# StepperBoard.net
KiCad netlist of a schematic drawn in EAGLE
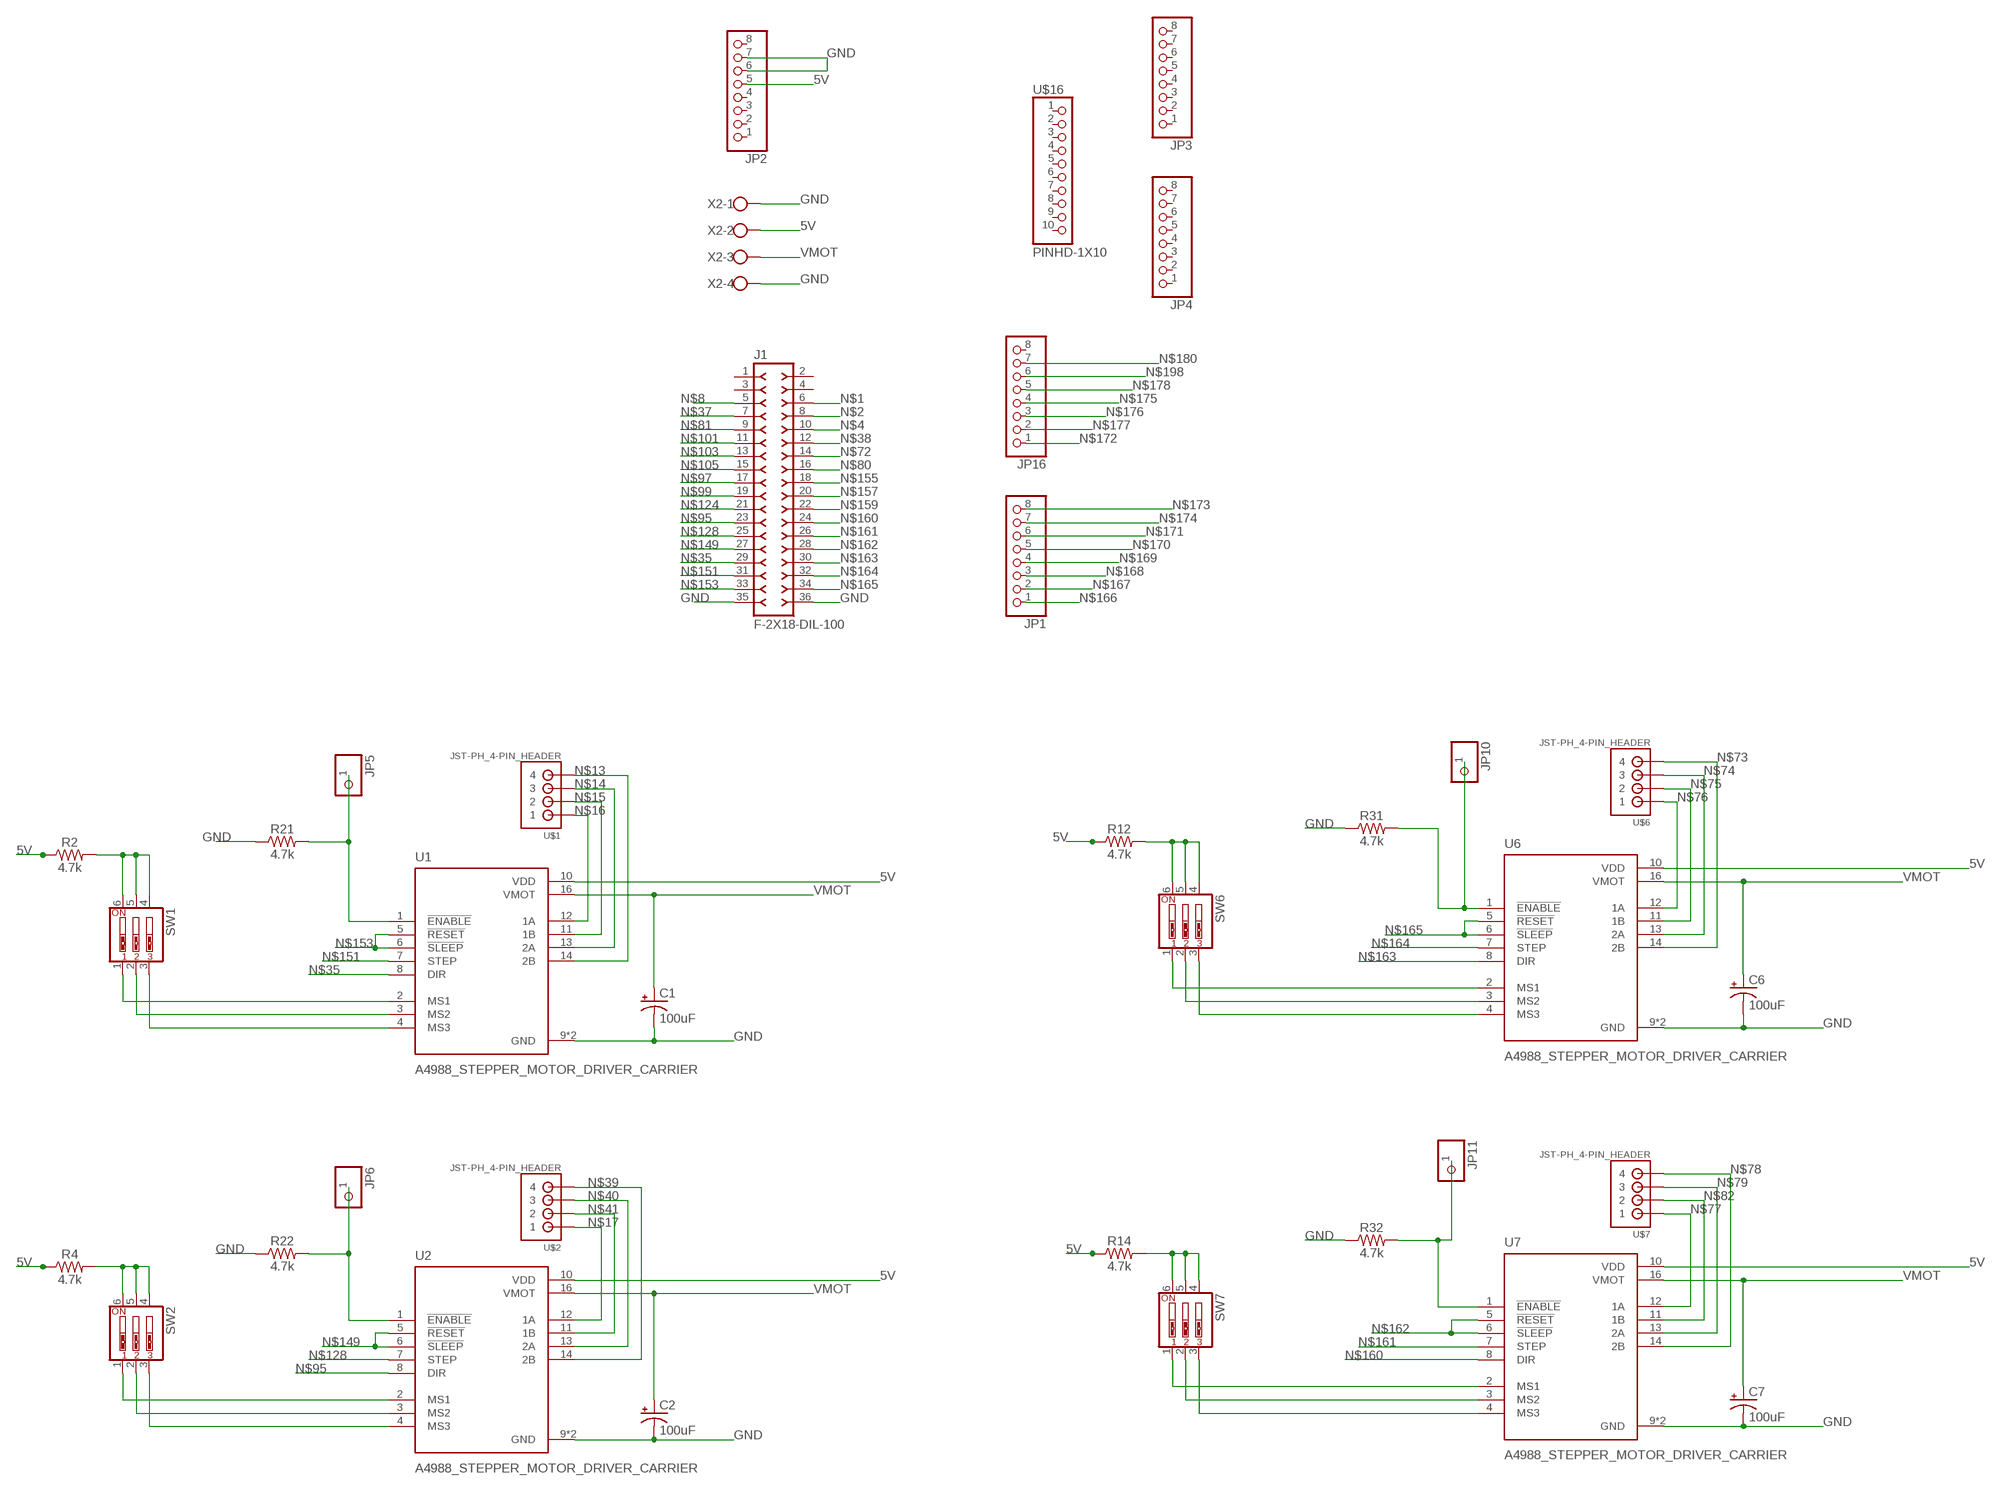
[diagram p0: schematic, sheet 1, part 1 of 3]
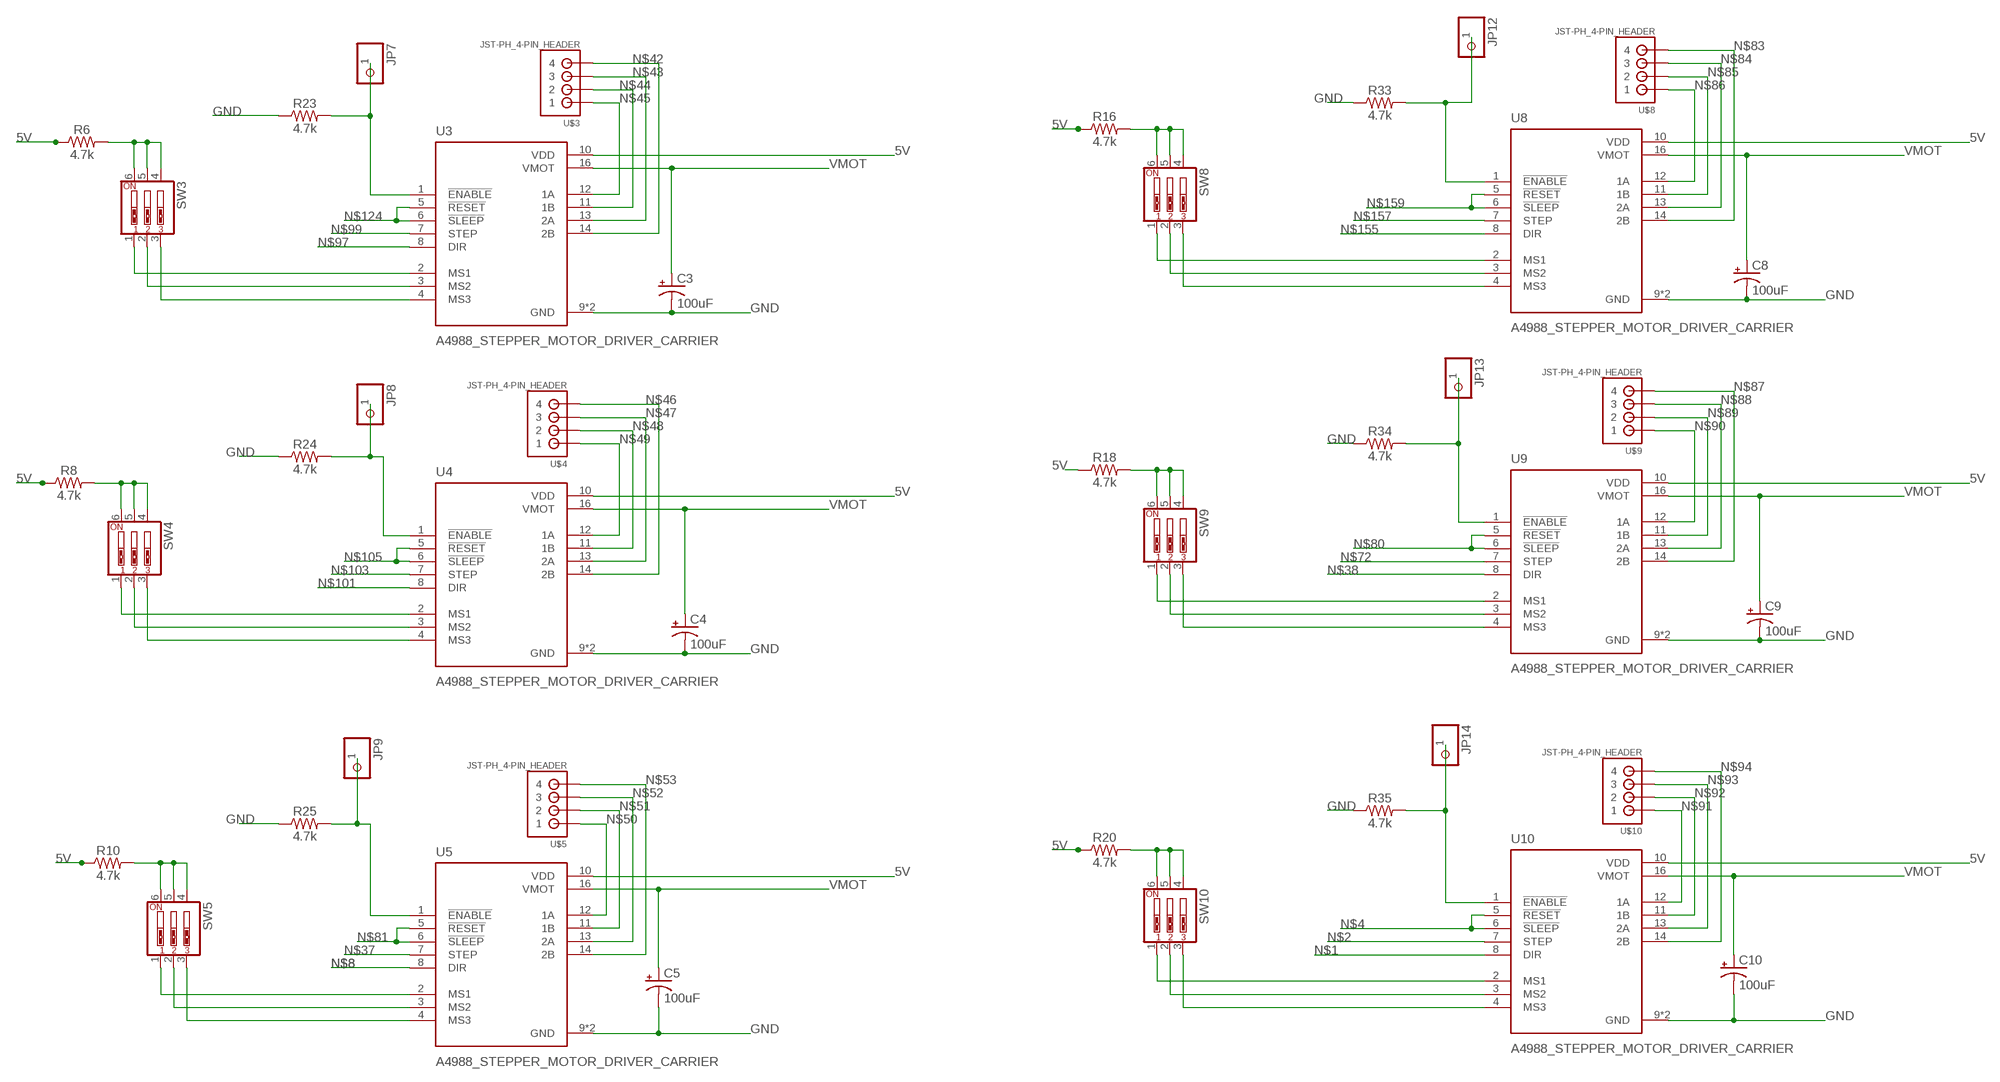
[diagram p1: schematic, sheet 1, part 2 of 3]
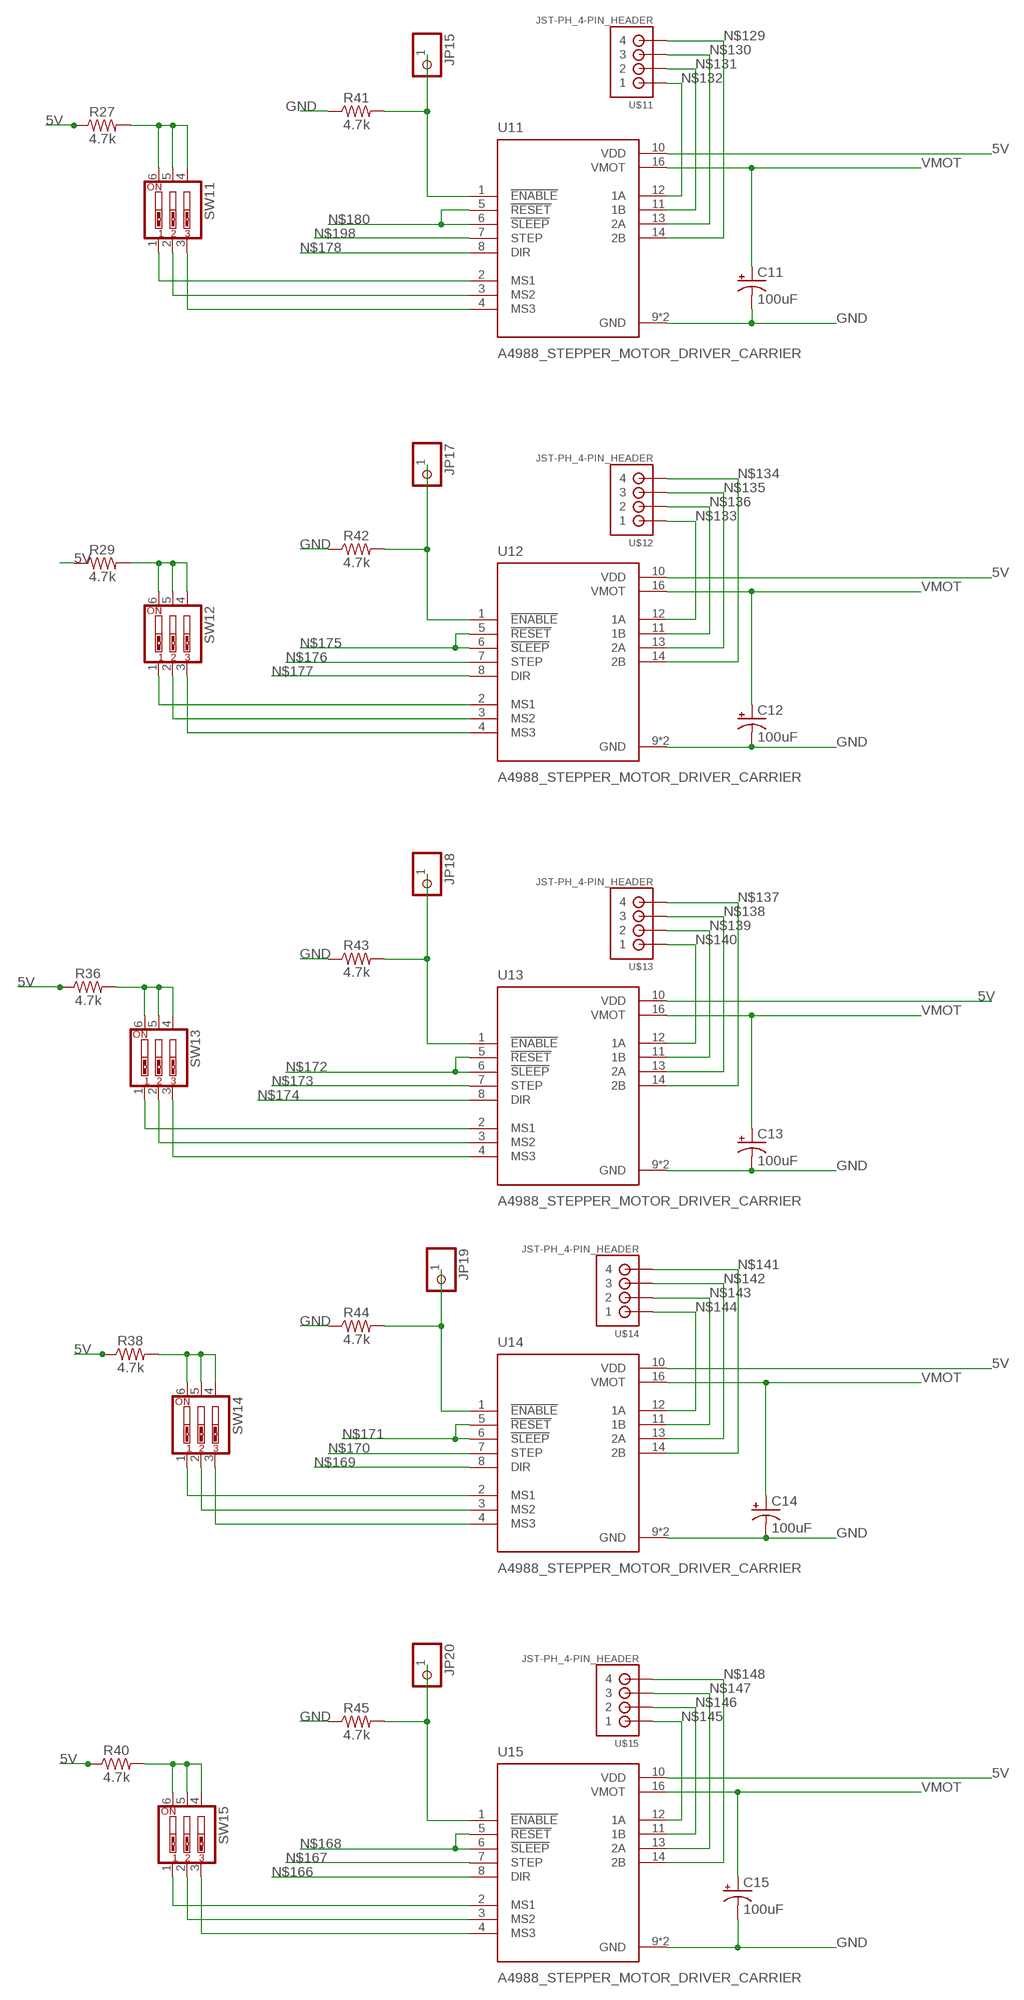
[diagram p2: schematic, sheet 1, part 3 of 3]

(export (version "E")
  (design (tool "Eeschema 10.0.6"))
  (components
    (comp (ref "C1")
      (value "100uF")
      (footprint "eagle-import:CPOL-RADIAL-2.5MM-6.5MM")
      (libsource (lib "eagle-import") (part "100UF-POLAR-RADIAL-2.5MM-25V-20%"))
    )
    (comp (ref "C2")
      (value "100uF")
      (footprint "eagle-import:CPOL-RADIAL-2.5MM-6.5MM")
      (libsource (lib "eagle-import") (part "100UF-POLAR-RADIAL-2.5MM-25V-20%"))
    )
    (comp (ref "C3")
      (value "100uF")
      (footprint "eagle-import:CPOL-RADIAL-2.5MM-6.5MM")
      (libsource (lib "eagle-import") (part "100UF-POLAR-RADIAL-2.5MM-25V-20%"))
    )
    (comp (ref "C4")
      (value "100uF")
      (footprint "eagle-import:CPOL-RADIAL-2.5MM-6.5MM")
      (libsource (lib "eagle-import") (part "100UF-POLAR-RADIAL-2.5MM-25V-20%"))
    )
    (comp (ref "C5")
      (value "100uF")
      (footprint "eagle-import:CPOL-RADIAL-2.5MM-6.5MM")
      (libsource (lib "eagle-import") (part "100UF-POLAR-RADIAL-2.5MM-25V-20%"))
    )
    (comp (ref "C6")
      (value "100uF")
      (footprint "eagle-import:CPOL-RADIAL-2.5MM-6.5MM")
      (libsource (lib "eagle-import") (part "100UF-POLAR-RADIAL-2.5MM-25V-20%"))
    )
    (comp (ref "C7")
      (value "100uF")
      (footprint "eagle-import:CPOL-RADIAL-2.5MM-6.5MM")
      (libsource (lib "eagle-import") (part "100UF-POLAR-RADIAL-2.5MM-25V-20%"))
    )
    (comp (ref "C8")
      (value "100uF")
      (footprint "eagle-import:CPOL-RADIAL-2.5MM-6.5MM")
      (libsource (lib "eagle-import") (part "100UF-POLAR-RADIAL-2.5MM-25V-20%"))
    )
    (comp (ref "C9")
      (value "100uF")
      (footprint "eagle-import:CPOL-RADIAL-2.5MM-6.5MM")
      (libsource (lib "eagle-import") (part "100UF-POLAR-RADIAL-2.5MM-25V-20%"))
    )
    (comp (ref "C10")
      (value "100uF")
      (footprint "eagle-import:CPOL-RADIAL-2.5MM-6.5MM")
      (libsource (lib "eagle-import") (part "100UF-POLAR-RADIAL-2.5MM-25V-20%"))
    )
    (comp (ref "C11")
      (value "100uF")
      (footprint "eagle-import:CPOL-RADIAL-2.5MM-6.5MM")
      (libsource (lib "eagle-import") (part "100UF-POLAR-RADIAL-2.5MM-25V-20%"))
    )
    (comp (ref "C12")
      (value "100uF")
      (footprint "eagle-import:CPOL-RADIAL-2.5MM-6.5MM")
      (libsource (lib "eagle-import") (part "100UF-POLAR-RADIAL-2.5MM-25V-20%"))
    )
    (comp (ref "C13")
      (value "100uF")
      (footprint "eagle-import:CPOL-RADIAL-2.5MM-6.5MM")
      (libsource (lib "eagle-import") (part "100UF-POLAR-RADIAL-2.5MM-25V-20%"))
    )
    (comp (ref "C14")
      (value "100uF")
      (footprint "eagle-import:CPOL-RADIAL-2.5MM-6.5MM")
      (libsource (lib "eagle-import") (part "100UF-POLAR-RADIAL-2.5MM-25V-20%"))
    )
    (comp (ref "C15")
      (value "100uF")
      (footprint "eagle-import:CPOL-RADIAL-2.5MM-6.5MM")
      (libsource (lib "eagle-import") (part "100UF-POLAR-RADIAL-2.5MM-25V-20%"))
    )
    (comp (ref "J1")
      (value "F-2X18-DIL-100")
      (footprint "eagle-import:DIL-100-2X18")
      (libsource (lib "eagle-import") (part "F-2X18-DIL-100"))
    )
    (comp (ref "JP1")
      (value "PINHD-1X8")
      (footprint "eagle-import:1X08")
      (libsource (lib "eagle-import") (part "PINHD-1X8"))
    )
    (comp (ref "JP2")
      (value "PINHD-1X8")
      (footprint "eagle-import:1X08")
      (libsource (lib "eagle-import") (part "PINHD-1X8"))
    )
    (comp (ref "JP3")
      (value "PINHD-1X8")
      (footprint "eagle-import:1X08")
      (libsource (lib "eagle-import") (part "PINHD-1X8"))
    )
    (comp (ref "JP4")
      (value "PINHD-1X8")
      (footprint "eagle-import:1X08")
      (libsource (lib "eagle-import") (part "PINHD-1X8"))
    )
    (comp (ref "JP5")
      (value "PINHD-1X1")
      (footprint "eagle-import:1X01")
      (libsource (lib "eagle-import") (part "PINHD-1X1"))
    )
    (comp (ref "JP6")
      (value "PINHD-1X1")
      (footprint "eagle-import:1X01")
      (libsource (lib "eagle-import") (part "PINHD-1X1"))
    )
    (comp (ref "JP7")
      (value "PINHD-1X1")
      (footprint "eagle-import:1X01")
      (libsource (lib "eagle-import") (part "PINHD-1X1"))
    )
    (comp (ref "JP8")
      (value "PINHD-1X1")
      (footprint "eagle-import:1X01")
      (libsource (lib "eagle-import") (part "PINHD-1X1"))
    )
    (comp (ref "JP9")
      (value "PINHD-1X1")
      (footprint "eagle-import:1X01")
      (libsource (lib "eagle-import") (part "PINHD-1X1"))
    )
    (comp (ref "JP10")
      (value "PINHD-1X1")
      (footprint "eagle-import:1X01")
      (libsource (lib "eagle-import") (part "PINHD-1X1"))
    )
    (comp (ref "JP11")
      (value "PINHD-1X1")
      (footprint "eagle-import:1X01")
      (libsource (lib "eagle-import") (part "PINHD-1X1"))
    )
    (comp (ref "JP12")
      (value "PINHD-1X1")
      (footprint "eagle-import:1X01")
      (libsource (lib "eagle-import") (part "PINHD-1X1"))
    )
    (comp (ref "JP13")
      (value "PINHD-1X1")
      (footprint "eagle-import:1X01")
      (libsource (lib "eagle-import") (part "PINHD-1X1"))
    )
    (comp (ref "JP14")
      (value "PINHD-1X1")
      (footprint "eagle-import:1X01")
      (libsource (lib "eagle-import") (part "PINHD-1X1"))
    )
    (comp (ref "JP15")
      (value "PINHD-1X1")
      (footprint "eagle-import:1X01")
      (libsource (lib "eagle-import") (part "PINHD-1X1"))
    )
    (comp (ref "JP16")
      (value "PINHD-1X8")
      (footprint "eagle-import:1X08")
      (libsource (lib "eagle-import") (part "PINHD-1X8"))
    )
    (comp (ref "JP17")
      (value "PINHD-1X1")
      (footprint "eagle-import:1X01")
      (libsource (lib "eagle-import") (part "PINHD-1X1"))
    )
    (comp (ref "JP18")
      (value "PINHD-1X1")
      (footprint "eagle-import:1X01")
      (libsource (lib "eagle-import") (part "PINHD-1X1"))
    )
    (comp (ref "JP19")
      (value "PINHD-1X1")
      (footprint "eagle-import:1X01")
      (libsource (lib "eagle-import") (part "PINHD-1X1"))
    )
    (comp (ref "JP20")
      (value "PINHD-1X1")
      (footprint "eagle-import:1X01")
      (libsource (lib "eagle-import") (part "PINHD-1X1"))
    )
    (comp (ref "R2")
      (value "4.7k")
      (footprint "eagle-import:0603")
      (libsource (lib "eagle-import") (part "4.7KOHM-0603-1/10W-1%"))
    )
    (comp (ref "R4")
      (value "4.7k")
      (footprint "eagle-import:0603")
      (libsource (lib "eagle-import") (part "4.7KOHM-0603-1/10W-1%"))
    )
    (comp (ref "R6")
      (value "4.7k")
      (footprint "eagle-import:0603")
      (libsource (lib "eagle-import") (part "4.7KOHM-0603-1/10W-1%"))
    )
    (comp (ref "R8")
      (value "4.7k")
      (footprint "eagle-import:0603")
      (libsource (lib "eagle-import") (part "4.7KOHM-0603-1/10W-1%"))
    )
    (comp (ref "R10")
      (value "4.7k")
      (footprint "eagle-import:0603")
      (libsource (lib "eagle-import") (part "4.7KOHM-0603-1/10W-1%"))
    )
    (comp (ref "R12")
      (value "4.7k")
      (footprint "eagle-import:0603")
      (libsource (lib "eagle-import") (part "4.7KOHM-0603-1/10W-1%"))
    )
    (comp (ref "R14")
      (value "4.7k")
      (footprint "eagle-import:0603")
      (libsource (lib "eagle-import") (part "4.7KOHM-0603-1/10W-1%"))
    )
    (comp (ref "R16")
      (value "4.7k")
      (footprint "eagle-import:0603")
      (libsource (lib "eagle-import") (part "4.7KOHM-0603-1/10W-1%"))
    )
    (comp (ref "R18")
      (value "4.7k")
      (footprint "eagle-import:0603")
      (libsource (lib "eagle-import") (part "4.7KOHM-0603-1/10W-1%"))
    )
    (comp (ref "R20")
      (value "4.7k")
      (footprint "eagle-import:0603")
      (libsource (lib "eagle-import") (part "4.7KOHM-0603-1/10W-1%"))
    )
    (comp (ref "R21")
      (value "4.7k")
      (footprint "eagle-import:0603")
      (libsource (lib "eagle-import") (part "4.7KOHM-0603-1/10W-1%"))
    )
    (comp (ref "R22")
      (value "4.7k")
      (footprint "eagle-import:0603")
      (libsource (lib "eagle-import") (part "4.7KOHM-0603-1/10W-1%"))
    )
    (comp (ref "R23")
      (value "4.7k")
      (footprint "eagle-import:0603")
      (libsource (lib "eagle-import") (part "4.7KOHM-0603-1/10W-1%"))
    )
    (comp (ref "R24")
      (value "4.7k")
      (footprint "eagle-import:0603")
      (libsource (lib "eagle-import") (part "4.7KOHM-0603-1/10W-1%"))
    )
    (comp (ref "R25")
      (value "4.7k")
      (footprint "eagle-import:0603")
      (libsource (lib "eagle-import") (part "4.7KOHM-0603-1/10W-1%"))
    )
    (comp (ref "R27")
      (value "4.7k")
      (footprint "eagle-import:0603")
      (libsource (lib "eagle-import") (part "4.7KOHM-0603-1/10W-1%"))
    )
    (comp (ref "R29")
      (value "4.7k")
      (footprint "eagle-import:0603")
      (libsource (lib "eagle-import") (part "4.7KOHM-0603-1/10W-1%"))
    )
    (comp (ref "R31")
      (value "4.7k")
      (footprint "eagle-import:0603")
      (libsource (lib "eagle-import") (part "4.7KOHM-0603-1/10W-1%"))
    )
    (comp (ref "R32")
      (value "4.7k")
      (footprint "eagle-import:0603")
      (libsource (lib "eagle-import") (part "4.7KOHM-0603-1/10W-1%"))
    )
    (comp (ref "R33")
      (value "4.7k")
      (footprint "eagle-import:0603")
      (libsource (lib "eagle-import") (part "4.7KOHM-0603-1/10W-1%"))
    )
    (comp (ref "R34")
      (value "4.7k")
      (footprint "eagle-import:0603")
      (libsource (lib "eagle-import") (part "4.7KOHM-0603-1/10W-1%"))
    )
    (comp (ref "R35")
      (value "4.7k")
      (footprint "eagle-import:0603")
      (libsource (lib "eagle-import") (part "4.7KOHM-0603-1/10W-1%"))
    )
    (comp (ref "R36")
      (value "4.7k")
      (footprint "eagle-import:0603")
      (libsource (lib "eagle-import") (part "4.7KOHM-0603-1/10W-1%"))
    )
    (comp (ref "R38")
      (value "4.7k")
      (footprint "eagle-import:0603")
      (libsource (lib "eagle-import") (part "4.7KOHM-0603-1/10W-1%"))
    )
    (comp (ref "R40")
      (value "4.7k")
      (footprint "eagle-import:0603")
      (libsource (lib "eagle-import") (part "4.7KOHM-0603-1/10W-1%"))
    )
    (comp (ref "R41")
      (value "4.7k")
      (footprint "eagle-import:0603")
      (libsource (lib "eagle-import") (part "4.7KOHM-0603-1/10W-1%"))
    )
    (comp (ref "R42")
      (value "4.7k")
      (footprint "eagle-import:0603")
      (libsource (lib "eagle-import") (part "4.7KOHM-0603-1/10W-1%"))
    )
    (comp (ref "R43")
      (value "4.7k")
      (footprint "eagle-import:0603")
      (libsource (lib "eagle-import") (part "4.7KOHM-0603-1/10W-1%"))
    )
    (comp (ref "R44")
      (value "4.7k")
      (footprint "eagle-import:0603")
      (libsource (lib "eagle-import") (part "4.7KOHM-0603-1/10W-1%"))
    )
    (comp (ref "R45")
      (value "4.7k")
      (footprint "eagle-import:0603")
      (libsource (lib "eagle-import") (part "4.7KOHM-0603-1/10W-1%"))
    )
    (comp (ref "SW1")
      (value "SW_DIP-3")
      (footprint "eagle-import:EDG-03")
      (libsource (lib "eagle-import") (part "SW_DIP-3"))
    )
    (comp (ref "SW2")
      (value "SW_DIP-3")
      (footprint "eagle-import:EDG-03")
      (libsource (lib "eagle-import") (part "SW_DIP-3"))
    )
    (comp (ref "SW3")
      (value "SW_DIP-3")
      (footprint "eagle-import:EDG-03")
      (libsource (lib "eagle-import") (part "SW_DIP-3"))
    )
    (comp (ref "SW4")
      (value "SW_DIP-3")
      (footprint "eagle-import:EDG-03")
      (libsource (lib "eagle-import") (part "SW_DIP-3"))
    )
    (comp (ref "SW5")
      (value "SW_DIP-3")
      (footprint "eagle-import:EDG-03")
      (libsource (lib "eagle-import") (part "SW_DIP-3"))
    )
    (comp (ref "SW6")
      (value "SW_DIP-3")
      (footprint "eagle-import:EDG-03")
      (libsource (lib "eagle-import") (part "SW_DIP-3"))
    )
    (comp (ref "SW7")
      (value "SW_DIP-3")
      (footprint "eagle-import:EDG-03")
      (libsource (lib "eagle-import") (part "SW_DIP-3"))
    )
    (comp (ref "SW8")
      (value "SW_DIP-3")
      (footprint "eagle-import:EDG-03")
      (libsource (lib "eagle-import") (part "SW_DIP-3"))
    )
    (comp (ref "SW9")
      (value "SW_DIP-3")
      (footprint "eagle-import:EDG-03")
      (libsource (lib "eagle-import") (part "SW_DIP-3"))
    )
    (comp (ref "SW10")
      (value "SW_DIP-3")
      (footprint "eagle-import:EDG-03")
      (libsource (lib "eagle-import") (part "SW_DIP-3"))
    )
    (comp (ref "SW11")
      (value "SW_DIP-3")
      (footprint "eagle-import:EDG-03")
      (libsource (lib "eagle-import") (part "SW_DIP-3"))
    )
    (comp (ref "SW12")
      (value "SW_DIP-3")
      (footprint "eagle-import:EDG-03")
      (libsource (lib "eagle-import") (part "SW_DIP-3"))
    )
    (comp (ref "SW13")
      (value "SW_DIP-3")
      (footprint "eagle-import:EDG-03")
      (libsource (lib "eagle-import") (part "SW_DIP-3"))
    )
    (comp (ref "SW14")
      (value "SW_DIP-3")
      (footprint "eagle-import:EDG-03")
      (libsource (lib "eagle-import") (part "SW_DIP-3"))
    )
    (comp (ref "SW15")
      (value "SW_DIP-3")
      (footprint "eagle-import:EDG-03")
      (libsource (lib "eagle-import") (part "SW_DIP-3"))
    )
    (comp (ref "U$1")
      (value "JST-PH_4-PIN_HEADER")
      (footprint "eagle-import:JST_B4B-PH_HEADER")
      (libsource (lib "eagle-import") (part "JST-PH_4-PIN_HEADER"))
    )
    (comp (ref "U$2")
      (value "JST-PH_4-PIN_HEADER")
      (footprint "eagle-import:JST_B4B-PH_HEADER")
      (libsource (lib "eagle-import") (part "JST-PH_4-PIN_HEADER"))
    )
    (comp (ref "U$3")
      (value "JST-PH_4-PIN_HEADER")
      (footprint "eagle-import:JST_B4B-PH_HEADER")
      (libsource (lib "eagle-import") (part "JST-PH_4-PIN_HEADER"))
    )
    (comp (ref "U$4")
      (value "JST-PH_4-PIN_HEADER")
      (footprint "eagle-import:JST_B4B-PH_HEADER")
      (libsource (lib "eagle-import") (part "JST-PH_4-PIN_HEADER"))
    )
    (comp (ref "U$5")
      (value "JST-PH_4-PIN_HEADER")
      (footprint "eagle-import:JST_B4B-PH_HEADER")
      (libsource (lib "eagle-import") (part "JST-PH_4-PIN_HEADER"))
    )
    (comp (ref "U$6")
      (value "JST-PH_4-PIN_HEADER")
      (footprint "eagle-import:JST_B4B-PH_HEADER")
      (libsource (lib "eagle-import") (part "JST-PH_4-PIN_HEADER"))
    )
    (comp (ref "U$7")
      (value "JST-PH_4-PIN_HEADER")
      (footprint "eagle-import:JST_B4B-PH_HEADER")
      (libsource (lib "eagle-import") (part "JST-PH_4-PIN_HEADER"))
    )
    (comp (ref "U$8")
      (value "JST-PH_4-PIN_HEADER")
      (footprint "eagle-import:JST_B4B-PH_HEADER")
      (libsource (lib "eagle-import") (part "JST-PH_4-PIN_HEADER"))
    )
    (comp (ref "U$9")
      (value "JST-PH_4-PIN_HEADER")
      (footprint "eagle-import:JST_B4B-PH_HEADER")
      (libsource (lib "eagle-import") (part "JST-PH_4-PIN_HEADER"))
    )
    (comp (ref "U$10")
      (value "JST-PH_4-PIN_HEADER")
      (footprint "eagle-import:JST_B4B-PH_HEADER")
      (libsource (lib "eagle-import") (part "JST-PH_4-PIN_HEADER"))
    )
    (comp (ref "U$11")
      (value "JST-PH_4-PIN_HEADER")
      (footprint "eagle-import:JST_B4B-PH_HEADER")
      (libsource (lib "eagle-import") (part "JST-PH_4-PIN_HEADER"))
    )
    (comp (ref "U$12")
      (value "JST-PH_4-PIN_HEADER")
      (footprint "eagle-import:JST_B4B-PH_HEADER")
      (libsource (lib "eagle-import") (part "JST-PH_4-PIN_HEADER"))
    )
    (comp (ref "U$13")
      (value "JST-PH_4-PIN_HEADER")
      (footprint "eagle-import:JST_B4B-PH_HEADER")
      (libsource (lib "eagle-import") (part "JST-PH_4-PIN_HEADER"))
    )
    (comp (ref "U$14")
      (value "JST-PH_4-PIN_HEADER")
      (footprint "eagle-import:JST_B4B-PH_HEADER")
      (libsource (lib "eagle-import") (part "JST-PH_4-PIN_HEADER"))
    )
    (comp (ref "U$15")
      (value "JST-PH_4-PIN_HEADER")
      (footprint "eagle-import:JST_B4B-PH_HEADER")
      (libsource (lib "eagle-import") (part "JST-PH_4-PIN_HEADER"))
    )
    (comp (ref "U$16")
      (value "PINHD-1X10")
      (footprint "eagle-import:1X10-BIG")
      (libsource (lib "eagle-import") (part "PINHD-1X10"))
    )
    (comp (ref "U1")
      (value "A4988_STEPPER_MOTOR_DRIVER_CARRIER")
      (footprint "eagle-import:MODULE_A4988_STEPPER_MOTOR_DRIVER_CARRIER")
      (fields (field (name "MF") "Pololu") (field (name "MP") "A4988 STEPPER MOTOR DRIVER CARRIER"))
      (libsource (lib "eagle-import") (part "A4988_STEPPER_MOTOR_DRIVER_CARRIER"))
    )
    (comp (ref "U2")
      (value "A4988_STEPPER_MOTOR_DRIVER_CARRIER")
      (footprint "eagle-import:MODULE_A4988_STEPPER_MOTOR_DRIVER_CARRIER")
      (fields (field (name "MF") "Pololu") (field (name "MP") "A4988 STEPPER MOTOR DRIVER CARRIER"))
      (libsource (lib "eagle-import") (part "A4988_STEPPER_MOTOR_DRIVER_CARRIER"))
    )
    (comp (ref "U3")
      (value "A4988_STEPPER_MOTOR_DRIVER_CARRIER")
      (footprint "eagle-import:MODULE_A4988_STEPPER_MOTOR_DRIVER_CARRIER")
      (fields (field (name "MF") "Pololu") (field (name "MP") "A4988 STEPPER MOTOR DRIVER CARRIER"))
      (libsource (lib "eagle-import") (part "A4988_STEPPER_MOTOR_DRIVER_CARRIER"))
    )
    (comp (ref "U4")
      (value "A4988_STEPPER_MOTOR_DRIVER_CARRIER")
      (footprint "eagle-import:MODULE_A4988_STEPPER_MOTOR_DRIVER_CARRIER")
      (fields (field (name "MF") "Pololu") (field (name "MP") "A4988 STEPPER MOTOR DRIVER CARRIER"))
      (libsource (lib "eagle-import") (part "A4988_STEPPER_MOTOR_DRIVER_CARRIER"))
    )
    (comp (ref "U5")
      (value "A4988_STEPPER_MOTOR_DRIVER_CARRIER")
      (footprint "eagle-import:MODULE_A4988_STEPPER_MOTOR_DRIVER_CARRIER")
      (fields (field (name "MF") "Pololu") (field (name "MP") "A4988 STEPPER MOTOR DRIVER CARRIER"))
      (libsource (lib "eagle-import") (part "A4988_STEPPER_MOTOR_DRIVER_CARRIER"))
    )
    (comp (ref "U6")
      (value "A4988_STEPPER_MOTOR_DRIVER_CARRIER")
      (footprint "eagle-import:MODULE_A4988_STEPPER_MOTOR_DRIVER_CARRIER")
      (fields (field (name "MF") "Pololu") (field (name "MP") "A4988 STEPPER MOTOR DRIVER CARRIER"))
      (libsource (lib "eagle-import") (part "A4988_STEPPER_MOTOR_DRIVER_CARRIER"))
    )
    (comp (ref "U7")
      (value "A4988_STEPPER_MOTOR_DRIVER_CARRIER")
      (footprint "eagle-import:MODULE_A4988_STEPPER_MOTOR_DRIVER_CARRIER")
      (fields (field (name "MF") "Pololu") (field (name "MP") "A4988 STEPPER MOTOR DRIVER CARRIER"))
      (libsource (lib "eagle-import") (part "A4988_STEPPER_MOTOR_DRIVER_CARRIER"))
    )
    (comp (ref "U8")
      (value "A4988_STEPPER_MOTOR_DRIVER_CARRIER")
      (footprint "eagle-import:MODULE_A4988_STEPPER_MOTOR_DRIVER_CARRIER")
      (fields (field (name "MF") "Pololu") (field (name "MP") "A4988 STEPPER MOTOR DRIVER CARRIER"))
      (libsource (lib "eagle-import") (part "A4988_STEPPER_MOTOR_DRIVER_CARRIER"))
    )
    (comp (ref "U9")
      (value "A4988_STEPPER_MOTOR_DRIVER_CARRIER")
      (footprint "eagle-import:MODULE_A4988_STEPPER_MOTOR_DRIVER_CARRIER")
      (fields (field (name "MF") "Pololu") (field (name "MP") "A4988 STEPPER MOTOR DRIVER CARRIER"))
      (libsource (lib "eagle-import") (part "A4988_STEPPER_MOTOR_DRIVER_CARRIER"))
    )
    (comp (ref "U10")
      (value "A4988_STEPPER_MOTOR_DRIVER_CARRIER")
      (footprint "eagle-import:MODULE_A4988_STEPPER_MOTOR_DRIVER_CARRIER")
      (fields (field (name "MF") "Pololu") (field (name "MP") "A4988 STEPPER MOTOR DRIVER CARRIER"))
      (libsource (lib "eagle-import") (part "A4988_STEPPER_MOTOR_DRIVER_CARRIER"))
    )
    (comp (ref "U11")
      (value "A4988_STEPPER_MOTOR_DRIVER_CARRIER")
      (footprint "eagle-import:MODULE_A4988_STEPPER_MOTOR_DRIVER_CARRIER")
      (fields (field (name "MF") "Pololu") (field (name "MP") "A4988 STEPPER MOTOR DRIVER CARRIER"))
      (libsource (lib "eagle-import") (part "A4988_STEPPER_MOTOR_DRIVER_CARRIER"))
    )
    (comp (ref "U12")
      (value "A4988_STEPPER_MOTOR_DRIVER_CARRIER")
      (footprint "eagle-import:MODULE_A4988_STEPPER_MOTOR_DRIVER_CARRIER")
      (fields (field (name "MF") "Pololu") (field (name "MP") "A4988 STEPPER MOTOR DRIVER CARRIER"))
      (libsource (lib "eagle-import") (part "A4988_STEPPER_MOTOR_DRIVER_CARRIER"))
    )
    (comp (ref "U13")
      (value "A4988_STEPPER_MOTOR_DRIVER_CARRIER")
      (footprint "eagle-import:MODULE_A4988_STEPPER_MOTOR_DRIVER_CARRIER")
      (fields (field (name "MF") "Pololu") (field (name "MP") "A4988 STEPPER MOTOR DRIVER CARRIER"))
      (libsource (lib "eagle-import") (part "A4988_STEPPER_MOTOR_DRIVER_CARRIER"))
    )
    (comp (ref "U14")
      (value "A4988_STEPPER_MOTOR_DRIVER_CARRIER")
      (footprint "eagle-import:MODULE_A4988_STEPPER_MOTOR_DRIVER_CARRIER")
      (fields (field (name "MF") "Pololu") (field (name "MP") "A4988 STEPPER MOTOR DRIVER CARRIER"))
      (libsource (lib "eagle-import") (part "A4988_STEPPER_MOTOR_DRIVER_CARRIER"))
    )
    (comp (ref "U15")
      (value "A4988_STEPPER_MOTOR_DRIVER_CARRIER")
      (footprint "eagle-import:MODULE_A4988_STEPPER_MOTOR_DRIVER_CARRIER")
      (fields (field (name "MF") "Pololu") (field (name "MP") "A4988 STEPPER MOTOR DRIVER CARRIER"))
      (libsource (lib "eagle-import") (part "A4988_STEPPER_MOTOR_DRIVER_CARRIER"))
    )
    (comp (ref "X2")
      (value "W237-4")
      (footprint "eagle-import:W237-4")
      (libsource (lib "eagle-import") (part "W237-4"))
    )
  )
  (nets
    (net (code "1") (name "/5V") (class "Default")
      (node (ref "JP2") (pin "5") (pinfunction "5_5") (pintype "passive"))
      (node (ref "R10") (pin "1") (pinfunction "1_1") (pintype "passive"))
      (node (ref "R12") (pin "1") (pinfunction "1_1") (pintype "passive"))
      (node (ref "R14") (pin "1") (pinfunction "1_1") (pintype "passive"))
      (node (ref "R16") (pin "1") (pinfunction "1_1") (pintype "passive"))
      (node (ref "R18") (pin "1") (pinfunction "1_1") (pintype "passive"))
      (node (ref "R2") (pin "1") (pinfunction "1_1") (pintype "passive"))
      (node (ref "R20") (pin "1") (pinfunction "1_1") (pintype "passive"))
      (node (ref "R27") (pin "1") (pinfunction "1_1") (pintype "passive"))
      (node (ref "R29") (pin "1") (pinfunction "1_1") (pintype "passive"))
      (node (ref "R36") (pin "1") (pinfunction "1_1") (pintype "passive"))
      (node (ref "R38") (pin "1") (pinfunction "1_1") (pintype "passive"))
      (node (ref "R4") (pin "1") (pinfunction "1_1") (pintype "passive"))
      (node (ref "R40") (pin "1") (pinfunction "1_1") (pintype "passive"))
      (node (ref "R6") (pin "1") (pinfunction "1_1") (pintype "passive"))
      (node (ref "R8") (pin "1") (pinfunction "1_1") (pintype "passive"))
      (node (ref "U1") (pin "10") (pinfunction "VDD_10") (pintype "power_in"))
      (node (ref "U10") (pin "10") (pinfunction "VDD_10") (pintype "power_in"))
      (node (ref "U11") (pin "10") (pinfunction "VDD_10") (pintype "power_in"))
      (node (ref "U12") (pin "10") (pinfunction "VDD_10") (pintype "power_in"))
      (node (ref "U13") (pin "10") (pinfunction "VDD_10") (pintype "power_in"))
      (node (ref "U14") (pin "10") (pinfunction "VDD_10") (pintype "power_in"))
      (node (ref "U15") (pin "10") (pinfunction "VDD_10") (pintype "power_in"))
      (node (ref "U2") (pin "10") (pinfunction "VDD_10") (pintype "power_in"))
      (node (ref "U3") (pin "10") (pinfunction "VDD_10") (pintype "power_in"))
      (node (ref "U4") (pin "10") (pinfunction "VDD_10") (pintype "power_in"))
      (node (ref "U5") (pin "10") (pinfunction "VDD_10") (pintype "power_in"))
      (node (ref "U6") (pin "10") (pinfunction "VDD_10") (pintype "power_in"))
      (node (ref "U7") (pin "10") (pinfunction "VDD_10") (pintype "power_in"))
      (node (ref "U8") (pin "10") (pinfunction "VDD_10") (pintype "power_in"))
      (node (ref "U9") (pin "10") (pinfunction "VDD_10") (pintype "power_in"))
      (node (ref "X2") (pin "2") (pinfunction "KL_2") (pintype "passive"))
    )
    (net (code "2") (name "/GND") (class "Default")
      (node (ref "C1") (pin "2") (pinfunction "-_2") (pintype "passive"))
      (node (ref "C10") (pin "2") (pinfunction "-_2") (pintype "passive"))
      (node (ref "C11") (pin "2") (pinfunction "-_2") (pintype "passive"))
      (node (ref "C12") (pin "2") (pinfunction "-_2") (pintype "passive"))
      (node (ref "C13") (pin "2") (pinfunction "-_2") (pintype "passive"))
      (node (ref "C14") (pin "2") (pinfunction "-_2") (pintype "passive"))
      (node (ref "C15") (pin "2") (pinfunction "-_2") (pintype "passive"))
      (node (ref "C2") (pin "2") (pinfunction "-_2") (pintype "passive"))
      (node (ref "C3") (pin "2") (pinfunction "-_2") (pintype "passive"))
      (node (ref "C4") (pin "2") (pinfunction "-_2") (pintype "passive"))
      (node (ref "C5") (pin "2") (pinfunction "-_2") (pintype "passive"))
      (node (ref "C6") (pin "2") (pinfunction "-_2") (pintype "passive"))
      (node (ref "C7") (pin "2") (pinfunction "-_2") (pintype "passive"))
      (node (ref "C8") (pin "2") (pinfunction "-_2") (pintype "passive"))
      (node (ref "C9") (pin "2") (pinfunction "-_2") (pintype "passive"))
      (node (ref "J1") (pin "35") (pinfunction "35_35") (pintype "passive"))
      (node (ref "J1") (pin "36") (pinfunction "36_36") (pintype "passive"))
      (node (ref "JP2") (pin "6") (pinfunction "6_6") (pintype "passive"))
      (node (ref "JP2") (pin "7") (pinfunction "7_7") (pintype "passive"))
      (node (ref "R21") (pin "1") (pinfunction "1_1") (pintype "passive"))
      (node (ref "R22") (pin "1") (pinfunction "1_1") (pintype "passive"))
      (node (ref "R23") (pin "1") (pinfunction "1_1") (pintype "passive"))
      (node (ref "R24") (pin "1") (pinfunction "1_1") (pintype "passive"))
      (node (ref "R25") (pin "1") (pinfunction "1_1") (pintype "passive"))
      (node (ref "R31") (pin "1") (pinfunction "1_1") (pintype "passive"))
      (node (ref "R32") (pin "1") (pinfunction "1_1") (pintype "passive"))
      (node (ref "R33") (pin "1") (pinfunction "1_1") (pintype "passive"))
      (node (ref "R34") (pin "1") (pinfunction "1_1") (pintype "passive"))
      (node (ref "R35") (pin "1") (pinfunction "1_1") (pintype "passive"))
      (node (ref "R41") (pin "1") (pinfunction "1_1") (pintype "passive"))
      (node (ref "R42") (pin "1") (pinfunction "1_1") (pintype "passive"))
      (node (ref "R43") (pin "1") (pinfunction "1_1") (pintype "passive"))
      (node (ref "R44") (pin "1") (pinfunction "1_1") (pintype "passive"))
      (node (ref "R45") (pin "1") (pinfunction "1_1") (pintype "passive"))
      (node (ref "U1") (pin "15") (pinfunction "GND_15") (pintype "power_in"))
      (node (ref "U1") (pin "9") (pinfunction "GND_9") (pintype "power_in"))
      (node (ref "U10") (pin "15") (pinfunction "GND_15") (pintype "power_in"))
      (node (ref "U10") (pin "9") (pinfunction "GND_9") (pintype "power_in"))
      (node (ref "U11") (pin "15") (pinfunction "GND_15") (pintype "power_in"))
      (node (ref "U11") (pin "9") (pinfunction "GND_9") (pintype "power_in"))
      (node (ref "U12") (pin "15") (pinfunction "GND_15") (pintype "power_in"))
      (node (ref "U12") (pin "9") (pinfunction "GND_9") (pintype "power_in"))
      (node (ref "U13") (pin "15") (pinfunction "GND_15") (pintype "power_in"))
      (node (ref "U13") (pin "9") (pinfunction "GND_9") (pintype "power_in"))
      (node (ref "U14") (pin "15") (pinfunction "GND_15") (pintype "power_in"))
      (node (ref "U14") (pin "9") (pinfunction "GND_9") (pintype "power_in"))
      (node (ref "U15") (pin "15") (pinfunction "GND_15") (pintype "power_in"))
      (node (ref "U15") (pin "9") (pinfunction "GND_9") (pintype "power_in"))
      (node (ref "U2") (pin "15") (pinfunction "GND_15") (pintype "power_in"))
      (node (ref "U2") (pin "9") (pinfunction "GND_9") (pintype "power_in"))
      (node (ref "U3") (pin "15") (pinfunction "GND_15") (pintype "power_in"))
      (node (ref "U3") (pin "9") (pinfunction "GND_9") (pintype "power_in"))
      (node (ref "U4") (pin "15") (pinfunction "GND_15") (pintype "power_in"))
      (node (ref "U4") (pin "9") (pinfunction "GND_9") (pintype "power_in"))
      (node (ref "U5") (pin "15") (pinfunction "GND_15") (pintype "power_in"))
      (node (ref "U5") (pin "9") (pinfunction "GND_9") (pintype "power_in"))
      (node (ref "U6") (pin "15") (pinfunction "GND_15") (pintype "power_in"))
      (node (ref "U6") (pin "9") (pinfunction "GND_9") (pintype "power_in"))
      (node (ref "U7") (pin "15") (pinfunction "GND_15") (pintype "power_in"))
      (node (ref "U7") (pin "9") (pinfunction "GND_9") (pintype "power_in"))
      (node (ref "U8") (pin "15") (pinfunction "GND_15") (pintype "power_in"))
      (node (ref "U8") (pin "9") (pinfunction "GND_9") (pintype "power_in"))
      (node (ref "U9") (pin "15") (pinfunction "GND_15") (pintype "power_in"))
      (node (ref "U9") (pin "9") (pinfunction "GND_9") (pintype "power_in"))
      (node (ref "X2") (pin "1") (pinfunction "KL_1") (pintype "passive"))
      (node (ref "X2") (pin "4") (pinfunction "KL_4") (pintype "passive"))
    )
    (net (code "3") (name "/N$1") (class "Default")
      (node (ref "J1") (pin "6") (pinfunction "6_6") (pintype "passive"))
      (node (ref "U10") (pin "8") (pinfunction "DIR_8") (pintype "input"))
    )
    (net (code "4") (name "/N$2") (class "Default")
      (node (ref "J1") (pin "8") (pinfunction "8_8") (pintype "passive"))
      (node (ref "U10") (pin "7") (pinfunction "STEP_7") (pintype "input"))
    )
    (net (code "5") (name "/N$4") (class "Default")
      (node (ref "J1") (pin "10") (pinfunction "10_10") (pintype "passive"))
      (node (ref "U10") (pin "5") (pinfunction "~{RESET}_5") (pintype "input"))
      (node (ref "U10") (pin "6") (pinfunction "~{SLEEP}_6") (pintype "input"))
    )
    (net (code "6") (name "/N$8") (class "Default")
      (node (ref "J1") (pin "5") (pinfunction "5_5") (pintype "passive"))
      (node (ref "U5") (pin "8") (pinfunction "DIR_8") (pintype "input"))
    )
    (net (code "7") (name "/N$13") (class "Default")
      (node (ref "U$1") (pin "P4") (pinfunction "4_P4") (pintype "bidirectional"))
      (node (ref "U1") (pin "14") (pinfunction "2B_14") (pintype "output"))
    )
    (net (code "8") (name "/N$14") (class "Default")
      (node (ref "U$1") (pin "P3") (pinfunction "3_P3") (pintype "bidirectional"))
      (node (ref "U1") (pin "13") (pinfunction "2A_13") (pintype "output"))
    )
    (net (code "9") (name "/N$15") (class "Default")
      (node (ref "U$1") (pin "P2") (pinfunction "2_P2") (pintype "bidirectional"))
      (node (ref "U1") (pin "11") (pinfunction "1B_11") (pintype "output"))
    )
    (net (code "10") (name "/N$16") (class "Default")
      (node (ref "U$1") (pin "P1") (pinfunction "1_P1") (pintype "bidirectional"))
      (node (ref "U1") (pin "12") (pinfunction "1A_12") (pintype "output"))
    )
    (net (code "11") (name "/N$17") (class "Default")
      (node (ref "U$2") (pin "P1") (pinfunction "1_P1") (pintype "bidirectional"))
      (node (ref "U2") (pin "12") (pinfunction "1A_12") (pintype "output"))
    )
    (net (code "12") (name "/N$35") (class "Default")
      (node (ref "J1") (pin "29") (pinfunction "29_29") (pintype "passive"))
      (node (ref "U1") (pin "8") (pinfunction "DIR_8") (pintype "input"))
    )
    (net (code "13") (name "/N$37") (class "Default")
      (node (ref "J1") (pin "7") (pinfunction "7_7") (pintype "passive"))
      (node (ref "U5") (pin "7") (pinfunction "STEP_7") (pintype "input"))
    )
    (net (code "14") (name "/N$38") (class "Default")
      (node (ref "J1") (pin "12") (pinfunction "12_12") (pintype "passive"))
      (node (ref "U9") (pin "8") (pinfunction "DIR_8") (pintype "input"))
    )
    (net (code "15") (name "/N$39") (class "Default")
      (node (ref "U$2") (pin "P4") (pinfunction "4_P4") (pintype "bidirectional"))
      (node (ref "U2") (pin "14") (pinfunction "2B_14") (pintype "output"))
    )
    (net (code "16") (name "/N$40") (class "Default")
      (node (ref "U$2") (pin "P3") (pinfunction "3_P3") (pintype "bidirectional"))
      (node (ref "U2") (pin "13") (pinfunction "2A_13") (pintype "output"))
    )
    (net (code "17") (name "/N$41") (class "Default")
      (node (ref "U$2") (pin "P2") (pinfunction "2_P2") (pintype "bidirectional"))
      (node (ref "U2") (pin "11") (pinfunction "1B_11") (pintype "output"))
    )
    (net (code "18") (name "/N$42") (class "Default")
      (node (ref "U$3") (pin "P4") (pinfunction "4_P4") (pintype "bidirectional"))
      (node (ref "U3") (pin "14") (pinfunction "2B_14") (pintype "output"))
    )
    (net (code "19") (name "/N$43") (class "Default")
      (node (ref "U$3") (pin "P3") (pinfunction "3_P3") (pintype "bidirectional"))
      (node (ref "U3") (pin "13") (pinfunction "2A_13") (pintype "output"))
    )
    (net (code "20") (name "/N$44") (class "Default")
      (node (ref "U$3") (pin "P2") (pinfunction "2_P2") (pintype "bidirectional"))
      (node (ref "U3") (pin "11") (pinfunction "1B_11") (pintype "output"))
    )
    (net (code "21") (name "/N$45") (class "Default")
      (node (ref "U$3") (pin "P1") (pinfunction "1_P1") (pintype "bidirectional"))
      (node (ref "U3") (pin "12") (pinfunction "1A_12") (pintype "output"))
    )
    (net (code "22") (name "/N$46") (class "Default")
      (node (ref "U$4") (pin "P4") (pinfunction "4_P4") (pintype "bidirectional"))
      (node (ref "U4") (pin "14") (pinfunction "2B_14") (pintype "output"))
    )
    (net (code "23") (name "/N$47") (class "Default")
      (node (ref "U$4") (pin "P3") (pinfunction "3_P3") (pintype "bidirectional"))
      (node (ref "U4") (pin "13") (pinfunction "2A_13") (pintype "output"))
    )
    (net (code "24") (name "/N$48") (class "Default")
      (node (ref "U$4") (pin "P2") (pinfunction "2_P2") (pintype "bidirectional"))
      (node (ref "U4") (pin "11") (pinfunction "1B_11") (pintype "output"))
    )
    (net (code "25") (name "/N$49") (class "Default")
      (node (ref "U$4") (pin "P1") (pinfunction "1_P1") (pintype "bidirectional"))
      (node (ref "U4") (pin "12") (pinfunction "1A_12") (pintype "output"))
    )
    (net (code "26") (name "/N$50") (class "Default")
      (node (ref "U$5") (pin "P1") (pinfunction "1_P1") (pintype "bidirectional"))
      (node (ref "U5") (pin "12") (pinfunction "1A_12") (pintype "output"))
    )
    (net (code "27") (name "/N$51") (class "Default")
      (node (ref "U$5") (pin "P2") (pinfunction "2_P2") (pintype "bidirectional"))
      (node (ref "U5") (pin "11") (pinfunction "1B_11") (pintype "output"))
    )
    (net (code "28") (name "/N$52") (class "Default")
      (node (ref "U$5") (pin "P3") (pinfunction "3_P3") (pintype "bidirectional"))
      (node (ref "U5") (pin "13") (pinfunction "2A_13") (pintype "output"))
    )
    (net (code "29") (name "/N$53") (class "Default")
      (node (ref "U$5") (pin "P4") (pinfunction "4_P4") (pintype "bidirectional"))
      (node (ref "U5") (pin "14") (pinfunction "2B_14") (pintype "output"))
    )
    (net (code "30") (name "/N$72") (class "Default")
      (node (ref "J1") (pin "14") (pinfunction "14_14") (pintype "passive"))
      (node (ref "U9") (pin "7") (pinfunction "STEP_7") (pintype "input"))
    )
    (net (code "31") (name "/N$73") (class "Default")
      (node (ref "U$6") (pin "P4") (pinfunction "4_P4") (pintype "bidirectional"))
      (node (ref "U6") (pin "14") (pinfunction "2B_14") (pintype "output"))
    )
    (net (code "32") (name "/N$74") (class "Default")
      (node (ref "U$6") (pin "P3") (pinfunction "3_P3") (pintype "bidirectional"))
      (node (ref "U6") (pin "13") (pinfunction "2A_13") (pintype "output"))
    )
    (net (code "33") (name "/N$75") (class "Default")
      (node (ref "U$6") (pin "P2") (pinfunction "2_P2") (pintype "bidirectional"))
      (node (ref "U6") (pin "11") (pinfunction "1B_11") (pintype "output"))
    )
    (net (code "34") (name "/N$76") (class "Default")
      (node (ref "U$6") (pin "P1") (pinfunction "1_P1") (pintype "bidirectional"))
      (node (ref "U6") (pin "12") (pinfunction "1A_12") (pintype "output"))
    )
    (net (code "35") (name "/N$77") (class "Default")
      (node (ref "U$7") (pin "P1") (pinfunction "1_P1") (pintype "bidirectional"))
      (node (ref "U7") (pin "12") (pinfunction "1A_12") (pintype "output"))
    )
    (net (code "36") (name "/N$78") (class "Default")
      (node (ref "U$7") (pin "P4") (pinfunction "4_P4") (pintype "bidirectional"))
      (node (ref "U7") (pin "14") (pinfunction "2B_14") (pintype "output"))
    )
    (net (code "37") (name "/N$79") (class "Default")
      (node (ref "U$7") (pin "P3") (pinfunction "3_P3") (pintype "bidirectional"))
      (node (ref "U7") (pin "13") (pinfunction "2A_13") (pintype "output"))
    )
    (net (code "38") (name "/N$80") (class "Default")
      (node (ref "J1") (pin "16") (pinfunction "16_16") (pintype "passive"))
      (node (ref "U9") (pin "5") (pinfunction "~{RESET}_5") (pintype "input"))
      (node (ref "U9") (pin "6") (pinfunction "~{SLEEP}_6") (pintype "input"))
    )
    (net (code "39") (name "/N$81") (class "Default")
      (node (ref "J1") (pin "9") (pinfunction "9_9") (pintype "passive"))
      (node (ref "U5") (pin "5") (pinfunction "~{RESET}_5") (pintype "input"))
      (node (ref "U5") (pin "6") (pinfunction "~{SLEEP}_6") (pintype "input"))
    )
    (net (code "40") (name "/N$82") (class "Default")
      (node (ref "U$7") (pin "P2") (pinfunction "2_P2") (pintype "bidirectional"))
      (node (ref "U7") (pin "11") (pinfunction "1B_11") (pintype "output"))
    )
    (net (code "41") (name "/N$83") (class "Default")
      (node (ref "U$8") (pin "P4") (pinfunction "4_P4") (pintype "bidirectional"))
      (node (ref "U8") (pin "14") (pinfunction "2B_14") (pintype "output"))
    )
    (net (code "42") (name "/N$84") (class "Default")
      (node (ref "U$8") (pin "P3") (pinfunction "3_P3") (pintype "bidirectional"))
      (node (ref "U8") (pin "13") (pinfunction "2A_13") (pintype "output"))
    )
    (net (code "43") (name "/N$85") (class "Default")
      (node (ref "U$8") (pin "P2") (pinfunction "2_P2") (pintype "bidirectional"))
      (node (ref "U8") (pin "11") (pinfunction "1B_11") (pintype "output"))
    )
    (net (code "44") (name "/N$86") (class "Default")
      (node (ref "U$8") (pin "P1") (pinfunction "1_P1") (pintype "bidirectional"))
      (node (ref "U8") (pin "12") (pinfunction "1A_12") (pintype "output"))
    )
    (net (code "45") (name "/N$87") (class "Default")
      (node (ref "U$9") (pin "P4") (pinfunction "4_P4") (pintype "bidirectional"))
      (node (ref "U9") (pin "14") (pinfunction "2B_14") (pintype "output"))
    )
    (net (code "46") (name "/N$88") (class "Default")
      (node (ref "U$9") (pin "P3") (pinfunction "3_P3") (pintype "bidirectional"))
      (node (ref "U9") (pin "13") (pinfunction "2A_13") (pintype "output"))
    )
    (net (code "47") (name "/N$89") (class "Default")
      (node (ref "U$9") (pin "P2") (pinfunction "2_P2") (pintype "bidirectional"))
      (node (ref "U9") (pin "11") (pinfunction "1B_11") (pintype "output"))
    )
    (net (code "48") (name "/N$90") (class "Default")
      (node (ref "U$9") (pin "P1") (pinfunction "1_P1") (pintype "bidirectional"))
      (node (ref "U9") (pin "12") (pinfunction "1A_12") (pintype "output"))
    )
    (net (code "49") (name "/N$91") (class "Default")
      (node (ref "U$10") (pin "P1") (pinfunction "1_P1") (pintype "bidirectional"))
      (node (ref "U10") (pin "12") (pinfunction "1A_12") (pintype "output"))
    )
    (net (code "50") (name "/N$92") (class "Default")
      (node (ref "U$10") (pin "P2") (pinfunction "2_P2") (pintype "bidirectional"))
      (node (ref "U10") (pin "11") (pinfunction "1B_11") (pintype "output"))
    )
    (net (code "51") (name "/N$93") (class "Default")
      (node (ref "U$10") (pin "P3") (pinfunction "3_P3") (pintype "bidirectional"))
      (node (ref "U10") (pin "13") (pinfunction "2A_13") (pintype "output"))
    )
    (net (code "52") (name "/N$94") (class "Default")
      (node (ref "U$10") (pin "P4") (pinfunction "4_P4") (pintype "bidirectional"))
      (node (ref "U10") (pin "14") (pinfunction "2B_14") (pintype "output"))
    )
    (net (code "53") (name "/N$95") (class "Default")
      (node (ref "J1") (pin "23") (pinfunction "23_23") (pintype "passive"))
      (node (ref "U2") (pin "8") (pinfunction "DIR_8") (pintype "input"))
    )
    (net (code "54") (name "/N$97") (class "Default")
      (node (ref "J1") (pin "17") (pinfunction "17_17") (pintype "passive"))
      (node (ref "U3") (pin "8") (pinfunction "DIR_8") (pintype "input"))
    )
    (net (code "55") (name "/N$99") (class "Default")
      (node (ref "J1") (pin "19") (pinfunction "19_19") (pintype "passive"))
      (node (ref "U3") (pin "7") (pinfunction "STEP_7") (pintype "input"))
    )
    (net (code "56") (name "/N$101") (class "Default")
      (node (ref "J1") (pin "11") (pinfunction "11_11") (pintype "passive"))
      (node (ref "U4") (pin "8") (pinfunction "DIR_8") (pintype "input"))
    )
    (net (code "57") (name "/N$103") (class "Default")
      (node (ref "J1") (pin "13") (pinfunction "13_13") (pintype "passive"))
      (node (ref "U4") (pin "7") (pinfunction "STEP_7") (pintype "input"))
    )
    (net (code "58") (name "/N$105") (class "Default")
      (node (ref "J1") (pin "15") (pinfunction "15_15") (pintype "passive"))
      (node (ref "U4") (pin "5") (pinfunction "~{RESET}_5") (pintype "input"))
      (node (ref "U4") (pin "6") (pinfunction "~{SLEEP}_6") (pintype "input"))
    )
    (net (code "59") (name "/N$124") (class "Default")
      (node (ref "J1") (pin "21") (pinfunction "21_21") (pintype "passive"))
      (node (ref "U3") (pin "5") (pinfunction "~{RESET}_5") (pintype "input"))
      (node (ref "U3") (pin "6") (pinfunction "~{SLEEP}_6") (pintype "input"))
    )
    (net (code "60") (name "/N$128") (class "Default")
      (node (ref "J1") (pin "25") (pinfunction "25_25") (pintype "passive"))
      (node (ref "U2") (pin "7") (pinfunction "STEP_7") (pintype "input"))
    )
    (net (code "61") (name "/N$129") (class "Default")
      (node (ref "U$11") (pin "P4") (pinfunction "4_P4") (pintype "bidirectional"))
      (node (ref "U11") (pin "14") (pinfunction "2B_14") (pintype "output"))
    )
    (net (code "62") (name "/N$130") (class "Default")
      (node (ref "U$11") (pin "P3") (pinfunction "3_P3") (pintype "bidirectional"))
      (node (ref "U11") (pin "13") (pinfunction "2A_13") (pintype "output"))
    )
    (net (code "63") (name "/N$131") (class "Default")
      (node (ref "U$11") (pin "P2") (pinfunction "2_P2") (pintype "bidirectional"))
      (node (ref "U11") (pin "11") (pinfunction "1B_11") (pintype "output"))
    )
    (net (code "64") (name "/N$132") (class "Default")
      (node (ref "U$11") (pin "P1") (pinfunction "1_P1") (pintype "bidirectional"))
      (node (ref "U11") (pin "12") (pinfunction "1A_12") (pintype "output"))
    )
    (net (code "65") (name "/N$133") (class "Default")
      (node (ref "U$12") (pin "P1") (pinfunction "1_P1") (pintype "bidirectional"))
      (node (ref "U12") (pin "12") (pinfunction "1A_12") (pintype "output"))
    )
    (net (code "66") (name "/N$134") (class "Default")
      (node (ref "U$12") (pin "P4") (pinfunction "4_P4") (pintype "bidirectional"))
      (node (ref "U12") (pin "14") (pinfunction "2B_14") (pintype "output"))
    )
    (net (code "67") (name "/N$135") (class "Default")
      (node (ref "U$12") (pin "P3") (pinfunction "3_P3") (pintype "bidirectional"))
      (node (ref "U12") (pin "13") (pinfunction "2A_13") (pintype "output"))
    )
    (net (code "68") (name "/N$136") (class "Default")
      (node (ref "U$12") (pin "P2") (pinfunction "2_P2") (pintype "bidirectional"))
      (node (ref "U12") (pin "11") (pinfunction "1B_11") (pintype "output"))
    )
    (net (code "69") (name "/N$137") (class "Default")
      (node (ref "U$13") (pin "P4") (pinfunction "4_P4") (pintype "bidirectional"))
      (node (ref "U13") (pin "14") (pinfunction "2B_14") (pintype "output"))
    )
    (net (code "70") (name "/N$138") (class "Default")
      (node (ref "U$13") (pin "P3") (pinfunction "3_P3") (pintype "bidirectional"))
      (node (ref "U13") (pin "13") (pinfunction "2A_13") (pintype "output"))
    )
    (net (code "71") (name "/N$139") (class "Default")
      (node (ref "U$13") (pin "P2") (pinfunction "2_P2") (pintype "bidirectional"))
      (node (ref "U13") (pin "11") (pinfunction "1B_11") (pintype "output"))
    )
    (net (code "72") (name "/N$140") (class "Default")
      (node (ref "U$13") (pin "P1") (pinfunction "1_P1") (pintype "bidirectional"))
      (node (ref "U13") (pin "12") (pinfunction "1A_12") (pintype "output"))
    )
    (net (code "73") (name "/N$141") (class "Default")
      (node (ref "U$14") (pin "P4") (pinfunction "4_P4") (pintype "bidirectional"))
      (node (ref "U14") (pin "14") (pinfunction "2B_14") (pintype "output"))
    )
    (net (code "74") (name "/N$142") (class "Default")
      (node (ref "U$14") (pin "P3") (pinfunction "3_P3") (pintype "bidirectional"))
      (node (ref "U14") (pin "13") (pinfunction "2A_13") (pintype "output"))
    )
    (net (code "75") (name "/N$143") (class "Default")
      (node (ref "U$14") (pin "P2") (pinfunction "2_P2") (pintype "bidirectional"))
      (node (ref "U14") (pin "11") (pinfunction "1B_11") (pintype "output"))
    )
    (net (code "76") (name "/N$144") (class "Default")
      (node (ref "U$14") (pin "P1") (pinfunction "1_P1") (pintype "bidirectional"))
      (node (ref "U14") (pin "12") (pinfunction "1A_12") (pintype "output"))
    )
    (net (code "77") (name "/N$145") (class "Default")
      (node (ref "U$15") (pin "P1") (pinfunction "1_P1") (pintype "bidirectional"))
      (node (ref "U15") (pin "12") (pinfunction "1A_12") (pintype "output"))
    )
    (net (code "78") (name "/N$146") (class "Default")
      (node (ref "U$15") (pin "P2") (pinfunction "2_P2") (pintype "bidirectional"))
      (node (ref "U15") (pin "11") (pinfunction "1B_11") (pintype "output"))
    )
    (net (code "79") (name "/N$147") (class "Default")
      (node (ref "U$15") (pin "P3") (pinfunction "3_P3") (pintype "bidirectional"))
      (node (ref "U15") (pin "13") (pinfunction "2A_13") (pintype "output"))
    )
    (net (code "80") (name "/N$148") (class "Default")
      (node (ref "U$15") (pin "P4") (pinfunction "4_P4") (pintype "bidirectional"))
      (node (ref "U15") (pin "14") (pinfunction "2B_14") (pintype "output"))
    )
    (net (code "81") (name "/N$149") (class "Default")
      (node (ref "J1") (pin "27") (pinfunction "27_27") (pintype "passive"))
      (node (ref "U2") (pin "5") (pinfunction "~{RESET}_5") (pintype "input"))
      (node (ref "U2") (pin "6") (pinfunction "~{SLEEP}_6") (pintype "input"))
    )
    (net (code "82") (name "/N$151") (class "Default")
      (node (ref "J1") (pin "31") (pinfunction "31_31") (pintype "passive"))
      (node (ref "U1") (pin "7") (pinfunction "STEP_7") (pintype "input"))
    )
    (net (code "83") (name "/N$153") (class "Default")
      (node (ref "J1") (pin "33") (pinfunction "33_33") (pintype "passive"))
      (node (ref "U1") (pin "5") (pinfunction "~{RESET}_5") (pintype "input"))
      (node (ref "U1") (pin "6") (pinfunction "~{SLEEP}_6") (pintype "input"))
    )
    (net (code "84") (name "/N$155") (class "Default")
      (node (ref "J1") (pin "18") (pinfunction "18_18") (pintype "passive"))
      (node (ref "U8") (pin "8") (pinfunction "DIR_8") (pintype "input"))
    )
    (net (code "85") (name "/N$157") (class "Default")
      (node (ref "J1") (pin "20") (pinfunction "20_20") (pintype "passive"))
      (node (ref "U8") (pin "7") (pinfunction "STEP_7") (pintype "input"))
    )
    (net (code "86") (name "/N$159") (class "Default")
      (node (ref "J1") (pin "22") (pinfunction "22_22") (pintype "passive"))
      (node (ref "U8") (pin "5") (pinfunction "~{RESET}_5") (pintype "input"))
      (node (ref "U8") (pin "6") (pinfunction "~{SLEEP}_6") (pintype "input"))
    )
    (net (code "87") (name "/N$160") (class "Default")
      (node (ref "J1") (pin "24") (pinfunction "24_24") (pintype "passive"))
      (node (ref "U7") (pin "8") (pinfunction "DIR_8") (pintype "input"))
    )
    (net (code "88") (name "/N$161") (class "Default")
      (node (ref "J1") (pin "26") (pinfunction "26_26") (pintype "passive"))
      (node (ref "U7") (pin "7") (pinfunction "STEP_7") (pintype "input"))
    )
    (net (code "89") (name "/N$162") (class "Default")
      (node (ref "J1") (pin "28") (pinfunction "28_28") (pintype "passive"))
      (node (ref "U7") (pin "5") (pinfunction "~{RESET}_5") (pintype "input"))
      (node (ref "U7") (pin "6") (pinfunction "~{SLEEP}_6") (pintype "input"))
    )
    (net (code "90") (name "/N$163") (class "Default")
      (node (ref "J1") (pin "30") (pinfunction "30_30") (pintype "passive"))
      (node (ref "U6") (pin "8") (pinfunction "DIR_8") (pintype "input"))
    )
    (net (code "91") (name "/N$164") (class "Default")
      (node (ref "J1") (pin "32") (pinfunction "32_32") (pintype "passive"))
      (node (ref "U6") (pin "7") (pinfunction "STEP_7") (pintype "input"))
    )
    (net (code "92") (name "/N$165") (class "Default")
      (node (ref "J1") (pin "34") (pinfunction "34_34") (pintype "passive"))
      (node (ref "U6") (pin "5") (pinfunction "~{RESET}_5") (pintype "input"))
      (node (ref "U6") (pin "6") (pinfunction "~{SLEEP}_6") (pintype "input"))
    )
    (net (code "93") (name "/N$166") (class "Default")
      (node (ref "JP1") (pin "1") (pinfunction "1_1") (pintype "passive"))
      (node (ref "U15") (pin "8") (pinfunction "DIR_8") (pintype "input"))
    )
    (net (code "94") (name "/N$167") (class "Default")
      (node (ref "JP1") (pin "2") (pinfunction "2_2") (pintype "passive"))
      (node (ref "U15") (pin "7") (pinfunction "STEP_7") (pintype "input"))
    )
    (net (code "95") (name "/N$168") (class "Default")
      (node (ref "JP1") (pin "3") (pinfunction "3_3") (pintype "passive"))
      (node (ref "U15") (pin "5") (pinfunction "~{RESET}_5") (pintype "input"))
      (node (ref "U15") (pin "6") (pinfunction "~{SLEEP}_6") (pintype "input"))
    )
    (net (code "96") (name "/N$169") (class "Default")
      (node (ref "JP1") (pin "4") (pinfunction "4_4") (pintype "passive"))
      (node (ref "U14") (pin "8") (pinfunction "DIR_8") (pintype "input"))
    )
    (net (code "97") (name "/N$170") (class "Default")
      (node (ref "JP1") (pin "5") (pinfunction "5_5") (pintype "passive"))
      (node (ref "U14") (pin "7") (pinfunction "STEP_7") (pintype "input"))
    )
    (net (code "98") (name "/N$171") (class "Default")
      (node (ref "JP1") (pin "6") (pinfunction "6_6") (pintype "passive"))
      (node (ref "U14") (pin "5") (pinfunction "~{RESET}_5") (pintype "input"))
      (node (ref "U14") (pin "6") (pinfunction "~{SLEEP}_6") (pintype "input"))
    )
    (net (code "99") (name "/N$172") (class "Default")
      (node (ref "JP16") (pin "1") (pinfunction "1_1") (pintype "passive"))
      (node (ref "U13") (pin "5") (pinfunction "~{RESET}_5") (pintype "input"))
      (node (ref "U13") (pin "6") (pinfunction "~{SLEEP}_6") (pintype "input"))
    )
    (net (code "100") (name "/N$173") (class "Default")
      (node (ref "JP1") (pin "8") (pinfunction "8_8") (pintype "passive"))
      (node (ref "U13") (pin "7") (pinfunction "STEP_7") (pintype "input"))
    )
    (net (code "101") (name "/N$174") (class "Default")
      (node (ref "JP1") (pin "7") (pinfunction "7_7") (pintype "passive"))
      (node (ref "U13") (pin "8") (pinfunction "DIR_8") (pintype "input"))
    )
    (net (code "102") (name "/N$175") (class "Default")
      (node (ref "JP16") (pin "4") (pinfunction "4_4") (pintype "passive"))
      (node (ref "U12") (pin "5") (pinfunction "~{RESET}_5") (pintype "input"))
      (node (ref "U12") (pin "6") (pinfunction "~{SLEEP}_6") (pintype "input"))
    )
    (net (code "103") (name "/N$176") (class "Default")
      (node (ref "JP16") (pin "3") (pinfunction "3_3") (pintype "passive"))
      (node (ref "U12") (pin "7") (pinfunction "STEP_7") (pintype "input"))
    )
    (net (code "104") (name "/N$177") (class "Default")
      (node (ref "JP16") (pin "2") (pinfunction "2_2") (pintype "passive"))
      (node (ref "U12") (pin "8") (pinfunction "DIR_8") (pintype "input"))
    )
    (net (code "105") (name "/N$178") (class "Default")
      (node (ref "JP16") (pin "5") (pinfunction "5_5") (pintype "passive"))
      (node (ref "U11") (pin "8") (pinfunction "DIR_8") (pintype "input"))
    )
    (net (code "106") (name "/N$180") (class "Default")
      (node (ref "JP16") (pin "7") (pinfunction "7_7") (pintype "passive"))
      (node (ref "U11") (pin "5") (pinfunction "~{RESET}_5") (pintype "input"))
      (node (ref "U11") (pin "6") (pinfunction "~{SLEEP}_6") (pintype "input"))
    )
    (net (code "107") (name "/N$198") (class "Default")
      (node (ref "JP16") (pin "6") (pinfunction "6_6") (pintype "passive"))
      (node (ref "U11") (pin "7") (pinfunction "STEP_7") (pintype "input"))
    )
    (net (code "108") (name "/VMOT") (class "Default")
      (node (ref "C1") (pin "1") (pinfunction "+_1") (pintype "passive"))
      (node (ref "C10") (pin "1") (pinfunction "+_1") (pintype "passive"))
      (node (ref "C11") (pin "1") (pinfunction "+_1") (pintype "passive"))
      (node (ref "C12") (pin "1") (pinfunction "+_1") (pintype "passive"))
      (node (ref "C13") (pin "1") (pinfunction "+_1") (pintype "passive"))
      (node (ref "C14") (pin "1") (pinfunction "+_1") (pintype "passive"))
      (node (ref "C15") (pin "1") (pinfunction "+_1") (pintype "passive"))
      (node (ref "C2") (pin "1") (pinfunction "+_1") (pintype "passive"))
      (node (ref "C3") (pin "1") (pinfunction "+_1") (pintype "passive"))
      (node (ref "C4") (pin "1") (pinfunction "+_1") (pintype "passive"))
      (node (ref "C5") (pin "1") (pinfunction "+_1") (pintype "passive"))
      (node (ref "C6") (pin "1") (pinfunction "+_1") (pintype "passive"))
      (node (ref "C7") (pin "1") (pinfunction "+_1") (pintype "passive"))
      (node (ref "C8") (pin "1") (pinfunction "+_1") (pintype "passive"))
      (node (ref "C9") (pin "1") (pinfunction "+_1") (pintype "passive"))
      (node (ref "U1") (pin "16") (pinfunction "VMOT_16") (pintype "power_in"))
      (node (ref "U10") (pin "16") (pinfunction "VMOT_16") (pintype "power_in"))
      (node (ref "U11") (pin "16") (pinfunction "VMOT_16") (pintype "power_in"))
      (node (ref "U12") (pin "16") (pinfunction "VMOT_16") (pintype "power_in"))
      (node (ref "U13") (pin "16") (pinfunction "VMOT_16") (pintype "power_in"))
      (node (ref "U14") (pin "16") (pinfunction "VMOT_16") (pintype "power_in"))
      (node (ref "U15") (pin "16") (pinfunction "VMOT_16") (pintype "power_in"))
      (node (ref "U2") (pin "16") (pinfunction "VMOT_16") (pintype "power_in"))
      (node (ref "U3") (pin "16") (pinfunction "VMOT_16") (pintype "power_in"))
      (node (ref "U4") (pin "16") (pinfunction "VMOT_16") (pintype "power_in"))
      (node (ref "U5") (pin "16") (pinfunction "VMOT_16") (pintype "power_in"))
      (node (ref "U6") (pin "16") (pinfunction "VMOT_16") (pintype "power_in"))
      (node (ref "U7") (pin "16") (pinfunction "VMOT_16") (pintype "power_in"))
      (node (ref "U8") (pin "16") (pinfunction "VMOT_16") (pintype "power_in"))
      (node (ref "U9") (pin "16") (pinfunction "VMOT_16") (pintype "power_in"))
      (node (ref "X2") (pin "3") (pinfunction "KL_3") (pintype "passive"))
    )
    (net (code "109") (name "Net-(R2-Pad2)") (class "Default")
      (node (ref "R2") (pin "2") (pinfunction "2_2") (pintype "passive"))
      (node (ref "SW1") (pin "4") (pinfunction "4_4") (pintype "passive"))
      (node (ref "SW1") (pin "5") (pinfunction "5_5") (pintype "passive"))
      (node (ref "SW1") (pin "6") (pinfunction "6_6") (pintype "passive"))
    )
    (net (code "110") (name "Net-(R4-Pad2)") (class "Default")
      (node (ref "R4") (pin "2") (pinfunction "2_2") (pintype "passive"))
      (node (ref "SW2") (pin "4") (pinfunction "4_4") (pintype "passive"))
      (node (ref "SW2") (pin "5") (pinfunction "5_5") (pintype "passive"))
      (node (ref "SW2") (pin "6") (pinfunction "6_6") (pintype "passive"))
    )
    (net (code "111") (name "Net-(R6-Pad2)") (class "Default")
      (node (ref "R6") (pin "2") (pinfunction "2_2") (pintype "passive"))
      (node (ref "SW3") (pin "4") (pinfunction "4_4") (pintype "passive"))
      (node (ref "SW3") (pin "5") (pinfunction "5_5") (pintype "passive"))
      (node (ref "SW3") (pin "6") (pinfunction "6_6") (pintype "passive"))
    )
    (net (code "112") (name "Net-(R8-Pad2)") (class "Default")
      (node (ref "R8") (pin "2") (pinfunction "2_2") (pintype "passive"))
      (node (ref "SW4") (pin "4") (pinfunction "4_4") (pintype "passive"))
      (node (ref "SW4") (pin "5") (pinfunction "5_5") (pintype "passive"))
      (node (ref "SW4") (pin "6") (pinfunction "6_6") (pintype "passive"))
    )
    (net (code "113") (name "Net-(R10-Pad2)") (class "Default")
      (node (ref "R10") (pin "2") (pinfunction "2_2") (pintype "passive"))
      (node (ref "SW5") (pin "4") (pinfunction "4_4") (pintype "passive"))
      (node (ref "SW5") (pin "5") (pinfunction "5_5") (pintype "passive"))
      (node (ref "SW5") (pin "6") (pinfunction "6_6") (pintype "passive"))
    )
    (net (code "114") (name "Net-(R12-Pad2)") (class "Default")
      (node (ref "R12") (pin "2") (pinfunction "2_2") (pintype "passive"))
      (node (ref "SW6") (pin "4") (pinfunction "4_4") (pintype "passive"))
      (node (ref "SW6") (pin "5") (pinfunction "5_5") (pintype "passive"))
      (node (ref "SW6") (pin "6") (pinfunction "6_6") (pintype "passive"))
    )
    (net (code "115") (name "Net-(R14-Pad2)") (class "Default")
      (node (ref "R14") (pin "2") (pinfunction "2_2") (pintype "passive"))
      (node (ref "SW7") (pin "4") (pinfunction "4_4") (pintype "passive"))
      (node (ref "SW7") (pin "5") (pinfunction "5_5") (pintype "passive"))
      (node (ref "SW7") (pin "6") (pinfunction "6_6") (pintype "passive"))
    )
    (net (code "116") (name "Net-(R16-Pad2)") (class "Default")
      (node (ref "R16") (pin "2") (pinfunction "2_2") (pintype "passive"))
      (node (ref "SW8") (pin "4") (pinfunction "4_4") (pintype "passive"))
      (node (ref "SW8") (pin "5") (pinfunction "5_5") (pintype "passive"))
      (node (ref "SW8") (pin "6") (pinfunction "6_6") (pintype "passive"))
    )
    (net (code "117") (name "Net-(R18-Pad2)") (class "Default")
      (node (ref "R18") (pin "2") (pinfunction "2_2") (pintype "passive"))
      (node (ref "SW9") (pin "4") (pinfunction "4_4") (pintype "passive"))
      (node (ref "SW9") (pin "5") (pinfunction "5_5") (pintype "passive"))
      (node (ref "SW9") (pin "6") (pinfunction "6_6") (pintype "passive"))
    )
    (net (code "118") (name "Net-(R20-Pad2)") (class "Default")
      (node (ref "R20") (pin "2") (pinfunction "2_2") (pintype "passive"))
      (node (ref "SW10") (pin "4") (pinfunction "4_4") (pintype "passive"))
      (node (ref "SW10") (pin "5") (pinfunction "5_5") (pintype "passive"))
      (node (ref "SW10") (pin "6") (pinfunction "6_6") (pintype "passive"))
    )
    (net (code "119") (name "Net-(R27-Pad2)") (class "Default")
      (node (ref "R27") (pin "2") (pinfunction "2_2") (pintype "passive"))
      (node (ref "SW11") (pin "4") (pinfunction "4_4") (pintype "passive"))
      (node (ref "SW11") (pin "5") (pinfunction "5_5") (pintype "passive"))
      (node (ref "SW11") (pin "6") (pinfunction "6_6") (pintype "passive"))
    )
    (net (code "120") (name "Net-(R29-Pad2)") (class "Default")
      (node (ref "R29") (pin "2") (pinfunction "2_2") (pintype "passive"))
      (node (ref "SW12") (pin "4") (pinfunction "4_4") (pintype "passive"))
      (node (ref "SW12") (pin "5") (pinfunction "5_5") (pintype "passive"))
      (node (ref "SW12") (pin "6") (pinfunction "6_6") (pintype "passive"))
    )
    (net (code "121") (name "Net-(R36-Pad2)") (class "Default")
      (node (ref "R36") (pin "2") (pinfunction "2_2") (pintype "passive"))
      (node (ref "SW13") (pin "4") (pinfunction "4_4") (pintype "passive"))
      (node (ref "SW13") (pin "5") (pinfunction "5_5") (pintype "passive"))
      (node (ref "SW13") (pin "6") (pinfunction "6_6") (pintype "passive"))
    )
    (net (code "122") (name "Net-(R38-Pad2)") (class "Default")
      (node (ref "R38") (pin "2") (pinfunction "2_2") (pintype "passive"))
      (node (ref "SW14") (pin "4") (pinfunction "4_4") (pintype "passive"))
      (node (ref "SW14") (pin "5") (pinfunction "5_5") (pintype "passive"))
      (node (ref "SW14") (pin "6") (pinfunction "6_6") (pintype "passive"))
    )
    (net (code "123") (name "Net-(R40-Pad2)") (class "Default")
      (node (ref "R40") (pin "2") (pinfunction "2_2") (pintype "passive"))
      (node (ref "SW15") (pin "4") (pinfunction "4_4") (pintype "passive"))
      (node (ref "SW15") (pin "5") (pinfunction "5_5") (pintype "passive"))
      (node (ref "SW15") (pin "6") (pinfunction "6_6") (pintype "passive"))
    )
    (net (code "124") (name "Net-(U1-MS1)") (class "Default")
      (node (ref "SW1") (pin "1") (pinfunction "1_1") (pintype "passive"))
      (node (ref "U1") (pin "2") (pinfunction "MS1_2") (pintype "input"))
    )
    (net (code "125") (name "Net-(U1-MS2)") (class "Default")
      (node (ref "SW1") (pin "2") (pinfunction "2_2") (pintype "passive"))
      (node (ref "U1") (pin "3") (pinfunction "MS2_3") (pintype "input"))
    )
    (net (code "126") (name "Net-(U1-MS3)") (class "Default")
      (node (ref "SW1") (pin "3") (pinfunction "3_3") (pintype "passive"))
      (node (ref "U1") (pin "4") (pinfunction "MS3_4") (pintype "input"))
    )
    (net (code "127") (name "Net-(U1-~{ENABLE})") (class "Default")
      (node (ref "JP5") (pin "1") (pinfunction "1_1") (pintype "passive"))
      (node (ref "R21") (pin "2") (pinfunction "2_2") (pintype "passive"))
      (node (ref "U1") (pin "1") (pinfunction "~{ENABLE}_1") (pintype "input"))
    )
    (net (code "128") (name "Net-(U2-MS1)") (class "Default")
      (node (ref "SW2") (pin "1") (pinfunction "1_1") (pintype "passive"))
      (node (ref "U2") (pin "2") (pinfunction "MS1_2") (pintype "input"))
    )
    (net (code "129") (name "Net-(U2-MS2)") (class "Default")
      (node (ref "SW2") (pin "2") (pinfunction "2_2") (pintype "passive"))
      (node (ref "U2") (pin "3") (pinfunction "MS2_3") (pintype "input"))
    )
    (net (code "130") (name "Net-(U2-MS3)") (class "Default")
      (node (ref "SW2") (pin "3") (pinfunction "3_3") (pintype "passive"))
      (node (ref "U2") (pin "4") (pinfunction "MS3_4") (pintype "input"))
    )
    (net (code "131") (name "Net-(U2-~{ENABLE})") (class "Default")
      (node (ref "JP6") (pin "1") (pinfunction "1_1") (pintype "passive"))
      (node (ref "R22") (pin "2") (pinfunction "2_2") (pintype "passive"))
      (node (ref "U2") (pin "1") (pinfunction "~{ENABLE}_1") (pintype "input"))
    )
    (net (code "132") (name "Net-(U3-MS1)") (class "Default")
      (node (ref "SW3") (pin "1") (pinfunction "1_1") (pintype "passive"))
      (node (ref "U3") (pin "2") (pinfunction "MS1_2") (pintype "input"))
    )
    (net (code "133") (name "Net-(U3-MS2)") (class "Default")
      (node (ref "SW3") (pin "2") (pinfunction "2_2") (pintype "passive"))
      (node (ref "U3") (pin "3") (pinfunction "MS2_3") (pintype "input"))
    )
    (net (code "134") (name "Net-(U3-MS3)") (class "Default")
      (node (ref "SW3") (pin "3") (pinfunction "3_3") (pintype "passive"))
      (node (ref "U3") (pin "4") (pinfunction "MS3_4") (pintype "input"))
    )
    (net (code "135") (name "Net-(U3-~{ENABLE})") (class "Default")
      (node (ref "JP7") (pin "1") (pinfunction "1_1") (pintype "passive"))
      (node (ref "R23") (pin "2") (pinfunction "2_2") (pintype "passive"))
      (node (ref "U3") (pin "1") (pinfunction "~{ENABLE}_1") (pintype "input"))
    )
    (net (code "136") (name "Net-(U4-MS1)") (class "Default")
      (node (ref "SW4") (pin "1") (pinfunction "1_1") (pintype "passive"))
      (node (ref "U4") (pin "2") (pinfunction "MS1_2") (pintype "input"))
    )
    (net (code "137") (name "Net-(U4-MS2)") (class "Default")
      (node (ref "SW4") (pin "2") (pinfunction "2_2") (pintype "passive"))
      (node (ref "U4") (pin "3") (pinfunction "MS2_3") (pintype "input"))
    )
    (net (code "138") (name "Net-(U4-MS3)") (class "Default")
      (node (ref "SW4") (pin "3") (pinfunction "3_3") (pintype "passive"))
      (node (ref "U4") (pin "4") (pinfunction "MS3_4") (pintype "input"))
    )
    (net (code "139") (name "Net-(U4-~{ENABLE})") (class "Default")
      (node (ref "JP8") (pin "1") (pinfunction "1_1") (pintype "passive"))
      (node (ref "R24") (pin "2") (pinfunction "2_2") (pintype "passive"))
      (node (ref "U4") (pin "1") (pinfunction "~{ENABLE}_1") (pintype "input"))
    )
    (net (code "140") (name "Net-(U5-MS1)") (class "Default")
      (node (ref "SW5") (pin "1") (pinfunction "1_1") (pintype "passive"))
      (node (ref "U5") (pin "2") (pinfunction "MS1_2") (pintype "input"))
    )
    (net (code "141") (name "Net-(U5-MS2)") (class "Default")
      (node (ref "SW5") (pin "2") (pinfunction "2_2") (pintype "passive"))
      (node (ref "U5") (pin "3") (pinfunction "MS2_3") (pintype "input"))
    )
    (net (code "142") (name "Net-(U5-MS3)") (class "Default")
      (node (ref "SW5") (pin "3") (pinfunction "3_3") (pintype "passive"))
      (node (ref "U5") (pin "4") (pinfunction "MS3_4") (pintype "input"))
    )
    (net (code "143") (name "Net-(U5-~{ENABLE})") (class "Default")
      (node (ref "JP9") (pin "1") (pinfunction "1_1") (pintype "passive"))
      (node (ref "R25") (pin "2") (pinfunction "2_2") (pintype "passive"))
      (node (ref "U5") (pin "1") (pinfunction "~{ENABLE}_1") (pintype "input"))
    )
    (net (code "144") (name "Net-(U6-MS1)") (class "Default")
      (node (ref "SW6") (pin "1") (pinfunction "1_1") (pintype "passive"))
      (node (ref "U6") (pin "2") (pinfunction "MS1_2") (pintype "input"))
    )
    (net (code "145") (name "Net-(U6-MS2)") (class "Default")
      (node (ref "SW6") (pin "2") (pinfunction "2_2") (pintype "passive"))
      (node (ref "U6") (pin "3") (pinfunction "MS2_3") (pintype "input"))
    )
    (net (code "146") (name "Net-(U6-MS3)") (class "Default")
      (node (ref "SW6") (pin "3") (pinfunction "3_3") (pintype "passive"))
      (node (ref "U6") (pin "4") (pinfunction "MS3_4") (pintype "input"))
    )
    (net (code "147") (name "Net-(U6-~{ENABLE})") (class "Default")
      (node (ref "JP10") (pin "1") (pinfunction "1_1") (pintype "passive"))
      (node (ref "R31") (pin "2") (pinfunction "2_2") (pintype "passive"))
      (node (ref "U6") (pin "1") (pinfunction "~{ENABLE}_1") (pintype "input"))
    )
    (net (code "148") (name "Net-(U7-MS1)") (class "Default")
      (node (ref "SW7") (pin "1") (pinfunction "1_1") (pintype "passive"))
      (node (ref "U7") (pin "2") (pinfunction "MS1_2") (pintype "input"))
    )
    (net (code "149") (name "Net-(U7-MS2)") (class "Default")
      (node (ref "SW7") (pin "2") (pinfunction "2_2") (pintype "passive"))
      (node (ref "U7") (pin "3") (pinfunction "MS2_3") (pintype "input"))
    )
    (net (code "150") (name "Net-(U7-MS3)") (class "Default")
      (node (ref "SW7") (pin "3") (pinfunction "3_3") (pintype "passive"))
      (node (ref "U7") (pin "4") (pinfunction "MS3_4") (pintype "input"))
    )
    (net (code "151") (name "Net-(U7-~{ENABLE})") (class "Default")
      (node (ref "JP11") (pin "1") (pinfunction "1_1") (pintype "passive"))
      (node (ref "R32") (pin "2") (pinfunction "2_2") (pintype "passive"))
      (node (ref "U7") (pin "1") (pinfunction "~{ENABLE}_1") (pintype "input"))
    )
    (net (code "152") (name "Net-(U8-MS1)") (class "Default")
      (node (ref "SW8") (pin "1") (pinfunction "1_1") (pintype "passive"))
      (node (ref "U8") (pin "2") (pinfunction "MS1_2") (pintype "input"))
    )
    (net (code "153") (name "Net-(U8-MS2)") (class "Default")
      (node (ref "SW8") (pin "2") (pinfunction "2_2") (pintype "passive"))
      (node (ref "U8") (pin "3") (pinfunction "MS2_3") (pintype "input"))
    )
    (net (code "154") (name "Net-(U8-MS3)") (class "Default")
      (node (ref "SW8") (pin "3") (pinfunction "3_3") (pintype "passive"))
      (node (ref "U8") (pin "4") (pinfunction "MS3_4") (pintype "input"))
    )
    (net (code "155") (name "Net-(U8-~{ENABLE})") (class "Default")
      (node (ref "JP12") (pin "1") (pinfunction "1_1") (pintype "passive"))
      (node (ref "R33") (pin "2") (pinfunction "2_2") (pintype "passive"))
      (node (ref "U8") (pin "1") (pinfunction "~{ENABLE}_1") (pintype "input"))
    )
    (net (code "156") (name "Net-(U9-MS1)") (class "Default")
      (node (ref "SW9") (pin "1") (pinfunction "1_1") (pintype "passive"))
      (node (ref "U9") (pin "2") (pinfunction "MS1_2") (pintype "input"))
    )
    (net (code "157") (name "Net-(U9-MS2)") (class "Default")
      (node (ref "SW9") (pin "2") (pinfunction "2_2") (pintype "passive"))
      (node (ref "U9") (pin "3") (pinfunction "MS2_3") (pintype "input"))
    )
    (net (code "158") (name "Net-(U9-MS3)") (class "Default")
      (node (ref "SW9") (pin "3") (pinfunction "3_3") (pintype "passive"))
      (node (ref "U9") (pin "4") (pinfunction "MS3_4") (pintype "input"))
    )
    (net (code "159") (name "Net-(U9-~{ENABLE})") (class "Default")
      (node (ref "JP13") (pin "1") (pinfunction "1_1") (pintype "passive"))
      (node (ref "R34") (pin "2") (pinfunction "2_2") (pintype "passive"))
      (node (ref "U9") (pin "1") (pinfunction "~{ENABLE}_1") (pintype "input"))
    )
    (net (code "160") (name "Net-(U10-MS1)") (class "Default")
      (node (ref "SW10") (pin "1") (pinfunction "1_1") (pintype "passive"))
      (node (ref "U10") (pin "2") (pinfunction "MS1_2") (pintype "input"))
    )
    (net (code "161") (name "Net-(U10-MS2)") (class "Default")
      (node (ref "SW10") (pin "2") (pinfunction "2_2") (pintype "passive"))
      (node (ref "U10") (pin "3") (pinfunction "MS2_3") (pintype "input"))
    )
    (net (code "162") (name "Net-(U10-MS3)") (class "Default")
      (node (ref "SW10") (pin "3") (pinfunction "3_3") (pintype "passive"))
      (node (ref "U10") (pin "4") (pinfunction "MS3_4") (pintype "input"))
    )
    (net (code "163") (name "Net-(U10-~{ENABLE})") (class "Default")
      (node (ref "JP14") (pin "1") (pinfunction "1_1") (pintype "passive"))
      (node (ref "R35") (pin "2") (pinfunction "2_2") (pintype "passive"))
      (node (ref "U10") (pin "1") (pinfunction "~{ENABLE}_1") (pintype "input"))
    )
    (net (code "164") (name "Net-(U11-MS1)") (class "Default")
      (node (ref "SW11") (pin "1") (pinfunction "1_1") (pintype "passive"))
      (node (ref "U11") (pin "2") (pinfunction "MS1_2") (pintype "input"))
    )
    (net (code "165") (name "Net-(U11-MS2)") (class "Default")
      (node (ref "SW11") (pin "2") (pinfunction "2_2") (pintype "passive"))
      (node (ref "U11") (pin "3") (pinfunction "MS2_3") (pintype "input"))
    )
    (net (code "166") (name "Net-(U11-MS3)") (class "Default")
      (node (ref "SW11") (pin "3") (pinfunction "3_3") (pintype "passive"))
      (node (ref "U11") (pin "4") (pinfunction "MS3_4") (pintype "input"))
    )
    (net (code "167") (name "Net-(U11-~{ENABLE})") (class "Default")
      (node (ref "JP15") (pin "1") (pinfunction "1_1") (pintype "passive"))
      (node (ref "R41") (pin "2") (pinfunction "2_2") (pintype "passive"))
      (node (ref "U11") (pin "1") (pinfunction "~{ENABLE}_1") (pintype "input"))
    )
    (net (code "168") (name "Net-(U12-MS1)") (class "Default")
      (node (ref "SW12") (pin "1") (pinfunction "1_1") (pintype "passive"))
      (node (ref "U12") (pin "2") (pinfunction "MS1_2") (pintype "input"))
    )
    (net (code "169") (name "Net-(U12-MS2)") (class "Default")
      (node (ref "SW12") (pin "2") (pinfunction "2_2") (pintype "passive"))
      (node (ref "U12") (pin "3") (pinfunction "MS2_3") (pintype "input"))
    )
    (net (code "170") (name "Net-(U12-MS3)") (class "Default")
      (node (ref "SW12") (pin "3") (pinfunction "3_3") (pintype "passive"))
      (node (ref "U12") (pin "4") (pinfunction "MS3_4") (pintype "input"))
    )
    (net (code "171") (name "Net-(U12-~{ENABLE})") (class "Default")
      (node (ref "JP17") (pin "1") (pinfunction "1_1") (pintype "passive"))
      (node (ref "R42") (pin "2") (pinfunction "2_2") (pintype "passive"))
      (node (ref "U12") (pin "1") (pinfunction "~{ENABLE}_1") (pintype "input"))
    )
    (net (code "172") (name "Net-(U13-MS1)") (class "Default")
      (node (ref "SW13") (pin "1") (pinfunction "1_1") (pintype "passive"))
      (node (ref "U13") (pin "2") (pinfunction "MS1_2") (pintype "input"))
    )
    (net (code "173") (name "Net-(U13-MS2)") (class "Default")
      (node (ref "SW13") (pin "2") (pinfunction "2_2") (pintype "passive"))
      (node (ref "U13") (pin "3") (pinfunction "MS2_3") (pintype "input"))
    )
    (net (code "174") (name "Net-(U13-MS3)") (class "Default")
      (node (ref "SW13") (pin "3") (pinfunction "3_3") (pintype "passive"))
      (node (ref "U13") (pin "4") (pinfunction "MS3_4") (pintype "input"))
    )
    (net (code "175") (name "Net-(U13-~{ENABLE})") (class "Default")
      (node (ref "JP18") (pin "1") (pinfunction "1_1") (pintype "passive"))
      (node (ref "R43") (pin "2") (pinfunction "2_2") (pintype "passive"))
      (node (ref "U13") (pin "1") (pinfunction "~{ENABLE}_1") (pintype "input"))
    )
    (net (code "176") (name "Net-(U14-MS1)") (class "Default")
      (node (ref "SW14") (pin "1") (pinfunction "1_1") (pintype "passive"))
      (node (ref "U14") (pin "2") (pinfunction "MS1_2") (pintype "input"))
    )
    (net (code "177") (name "Net-(U14-MS2)") (class "Default")
      (node (ref "SW14") (pin "2") (pinfunction "2_2") (pintype "passive"))
      (node (ref "U14") (pin "3") (pinfunction "MS2_3") (pintype "input"))
    )
    (net (code "178") (name "Net-(U14-MS3)") (class "Default")
      (node (ref "SW14") (pin "3") (pinfunction "3_3") (pintype "passive"))
      (node (ref "U14") (pin "4") (pinfunction "MS3_4") (pintype "input"))
    )
    (net (code "179") (name "Net-(U14-~{ENABLE})") (class "Default")
      (node (ref "JP19") (pin "1") (pinfunction "1_1") (pintype "passive"))
      (node (ref "R44") (pin "2") (pinfunction "2_2") (pintype "passive"))
      (node (ref "U14") (pin "1") (pinfunction "~{ENABLE}_1") (pintype "input"))
    )
    (net (code "180") (name "Net-(U15-MS1)") (class "Default")
      (node (ref "SW15") (pin "1") (pinfunction "1_1") (pintype "passive"))
      (node (ref "U15") (pin "2") (pinfunction "MS1_2") (pintype "input"))
    )
    (net (code "181") (name "Net-(U15-MS2)") (class "Default")
      (node (ref "SW15") (pin "2") (pinfunction "2_2") (pintype "passive"))
      (node (ref "U15") (pin "3") (pinfunction "MS2_3") (pintype "input"))
    )
    (net (code "182") (name "Net-(U15-MS3)") (class "Default")
      (node (ref "SW15") (pin "3") (pinfunction "3_3") (pintype "passive"))
      (node (ref "U15") (pin "4") (pinfunction "MS3_4") (pintype "input"))
    )
    (net (code "183") (name "Net-(U15-~{ENABLE})") (class "Default")
      (node (ref "JP20") (pin "1") (pinfunction "1_1") (pintype "passive"))
      (node (ref "R45") (pin "2") (pinfunction "2_2") (pintype "passive"))
      (node (ref "U15") (pin "1") (pinfunction "~{ENABLE}_1") (pintype "input"))
    )
    (net (code "184") (name "unconnected-(J1-Pad1)") (class "Default")
      (node (ref "J1") (pin "1") (pinfunction "1_1") (pintype "passive"))
    )
    (net (code "185") (name "unconnected-(J1-Pad2)") (class "Default")
      (node (ref "J1") (pin "2") (pinfunction "2_2") (pintype "passive"))
    )
    (net (code "186") (name "unconnected-(J1-Pad3)") (class "Default")
      (node (ref "J1") (pin "3") (pinfunction "3_3") (pintype "passive"))
    )
    (net (code "187") (name "unconnected-(J1-Pad4)") (class "Default")
      (node (ref "J1") (pin "4") (pinfunction "4_4") (pintype "passive"))
    )
    (net (code "188") (name "unconnected-(JP2-Pad1)") (class "Default")
      (node (ref "JP2") (pin "1") (pinfunction "1_1") (pintype "passive"))
    )
    (net (code "189") (name "unconnected-(JP2-Pad2)") (class "Default")
      (node (ref "JP2") (pin "2") (pinfunction "2_2") (pintype "passive"))
    )
    (net (code "190") (name "unconnected-(JP2-Pad3)") (class "Default")
      (node (ref "JP2") (pin "3") (pinfunction "3_3") (pintype "passive"))
    )
    (net (code "191") (name "unconnected-(JP2-Pad4)") (class "Default")
      (node (ref "JP2") (pin "4") (pinfunction "4_4") (pintype "passive"))
    )
    (net (code "192") (name "unconnected-(JP2-Pad8)") (class "Default")
      (node (ref "JP2") (pin "8") (pinfunction "8_8") (pintype "passive"))
    )
    (net (code "193") (name "unconnected-(JP3-Pad1)") (class "Default")
      (node (ref "JP3") (pin "1") (pinfunction "1_1") (pintype "passive"))
    )
    (net (code "194") (name "unconnected-(JP3-Pad2)") (class "Default")
      (node (ref "JP3") (pin "2") (pinfunction "2_2") (pintype "passive"))
    )
    (net (code "195") (name "unconnected-(JP3-Pad3)") (class "Default")
      (node (ref "JP3") (pin "3") (pinfunction "3_3") (pintype "passive"))
    )
    (net (code "196") (name "unconnected-(JP3-Pad4)") (class "Default")
      (node (ref "JP3") (pin "4") (pinfunction "4_4") (pintype "passive"))
    )
    (net (code "197") (name "unconnected-(JP3-Pad5)") (class "Default")
      (node (ref "JP3") (pin "5") (pinfunction "5_5") (pintype "passive"))
    )
    (net (code "198") (name "unconnected-(JP3-Pad6)") (class "Default")
      (node (ref "JP3") (pin "6") (pinfunction "6_6") (pintype "passive"))
    )
    (net (code "199") (name "unconnected-(JP3-Pad7)") (class "Default")
      (node (ref "JP3") (pin "7") (pinfunction "7_7") (pintype "passive"))
    )
    (net (code "200") (name "unconnected-(JP3-Pad8)") (class "Default")
      (node (ref "JP3") (pin "8") (pinfunction "8_8") (pintype "passive"))
    )
    (net (code "201") (name "unconnected-(JP4-Pad1)") (class "Default")
      (node (ref "JP4") (pin "1") (pinfunction "1_1") (pintype "passive"))
    )
    (net (code "202") (name "unconnected-(JP4-Pad2)") (class "Default")
      (node (ref "JP4") (pin "2") (pinfunction "2_2") (pintype "passive"))
    )
    (net (code "203") (name "unconnected-(JP4-Pad3)") (class "Default")
      (node (ref "JP4") (pin "3") (pinfunction "3_3") (pintype "passive"))
    )
    (net (code "204") (name "unconnected-(JP4-Pad4)") (class "Default")
      (node (ref "JP4") (pin "4") (pinfunction "4_4") (pintype "passive"))
    )
    (net (code "205") (name "unconnected-(JP4-Pad5)") (class "Default")
      (node (ref "JP4") (pin "5") (pinfunction "5_5") (pintype "passive"))
    )
    (net (code "206") (name "unconnected-(JP4-Pad6)") (class "Default")
      (node (ref "JP4") (pin "6") (pinfunction "6_6") (pintype "passive"))
    )
    (net (code "207") (name "unconnected-(JP4-Pad7)") (class "Default")
      (node (ref "JP4") (pin "7") (pinfunction "7_7") (pintype "passive"))
    )
    (net (code "208") (name "unconnected-(JP4-Pad8)") (class "Default")
      (node (ref "JP4") (pin "8") (pinfunction "8_8") (pintype "passive"))
    )
    (net (code "209") (name "unconnected-(JP16-Pad8)") (class "Default")
      (node (ref "JP16") (pin "8") (pinfunction "8_8") (pintype "passive"))
    )
    (net (code "210") (name "unconnected-(U$16-Pad1)") (class "Default")
      (node (ref "U$16") (pin "1") (pinfunction "1_1") (pintype "passive"))
    )
    (net (code "211") (name "unconnected-(U$16-Pad2)") (class "Default")
      (node (ref "U$16") (pin "2") (pinfunction "2_2") (pintype "passive"))
    )
    (net (code "212") (name "unconnected-(U$16-Pad3)") (class "Default")
      (node (ref "U$16") (pin "3") (pinfunction "3_3") (pintype "passive"))
    )
    (net (code "213") (name "unconnected-(U$16-Pad4)") (class "Default")
      (node (ref "U$16") (pin "4") (pinfunction "4_4") (pintype "passive"))
    )
    (net (code "214") (name "unconnected-(U$16-Pad5)") (class "Default")
      (node (ref "U$16") (pin "5") (pinfunction "5_5") (pintype "passive"))
    )
    (net (code "215") (name "unconnected-(U$16-Pad6)") (class "Default")
      (node (ref "U$16") (pin "6") (pinfunction "6_6") (pintype "passive"))
    )
    (net (code "216") (name "unconnected-(U$16-Pad7)") (class "Default")
      (node (ref "U$16") (pin "7") (pinfunction "7_7") (pintype "passive"))
    )
    (net (code "217") (name "unconnected-(U$16-Pad8)") (class "Default")
      (node (ref "U$16") (pin "8") (pinfunction "8_8") (pintype "passive"))
    )
    (net (code "218") (name "unconnected-(U$16-Pad9)") (class "Default")
      (node (ref "U$16") (pin "9") (pinfunction "9_9") (pintype "passive"))
    )
    (net (code "219") (name "unconnected-(U$16-Pad10)") (class "Default")
      (node (ref "U$16") (pin "10") (pinfunction "10_10") (pintype "passive"))
    )
  )
)
